# ExtBoard-001_2024-04-03.net
KiCad netlist of a schematic drawn in EasyEDA Pro
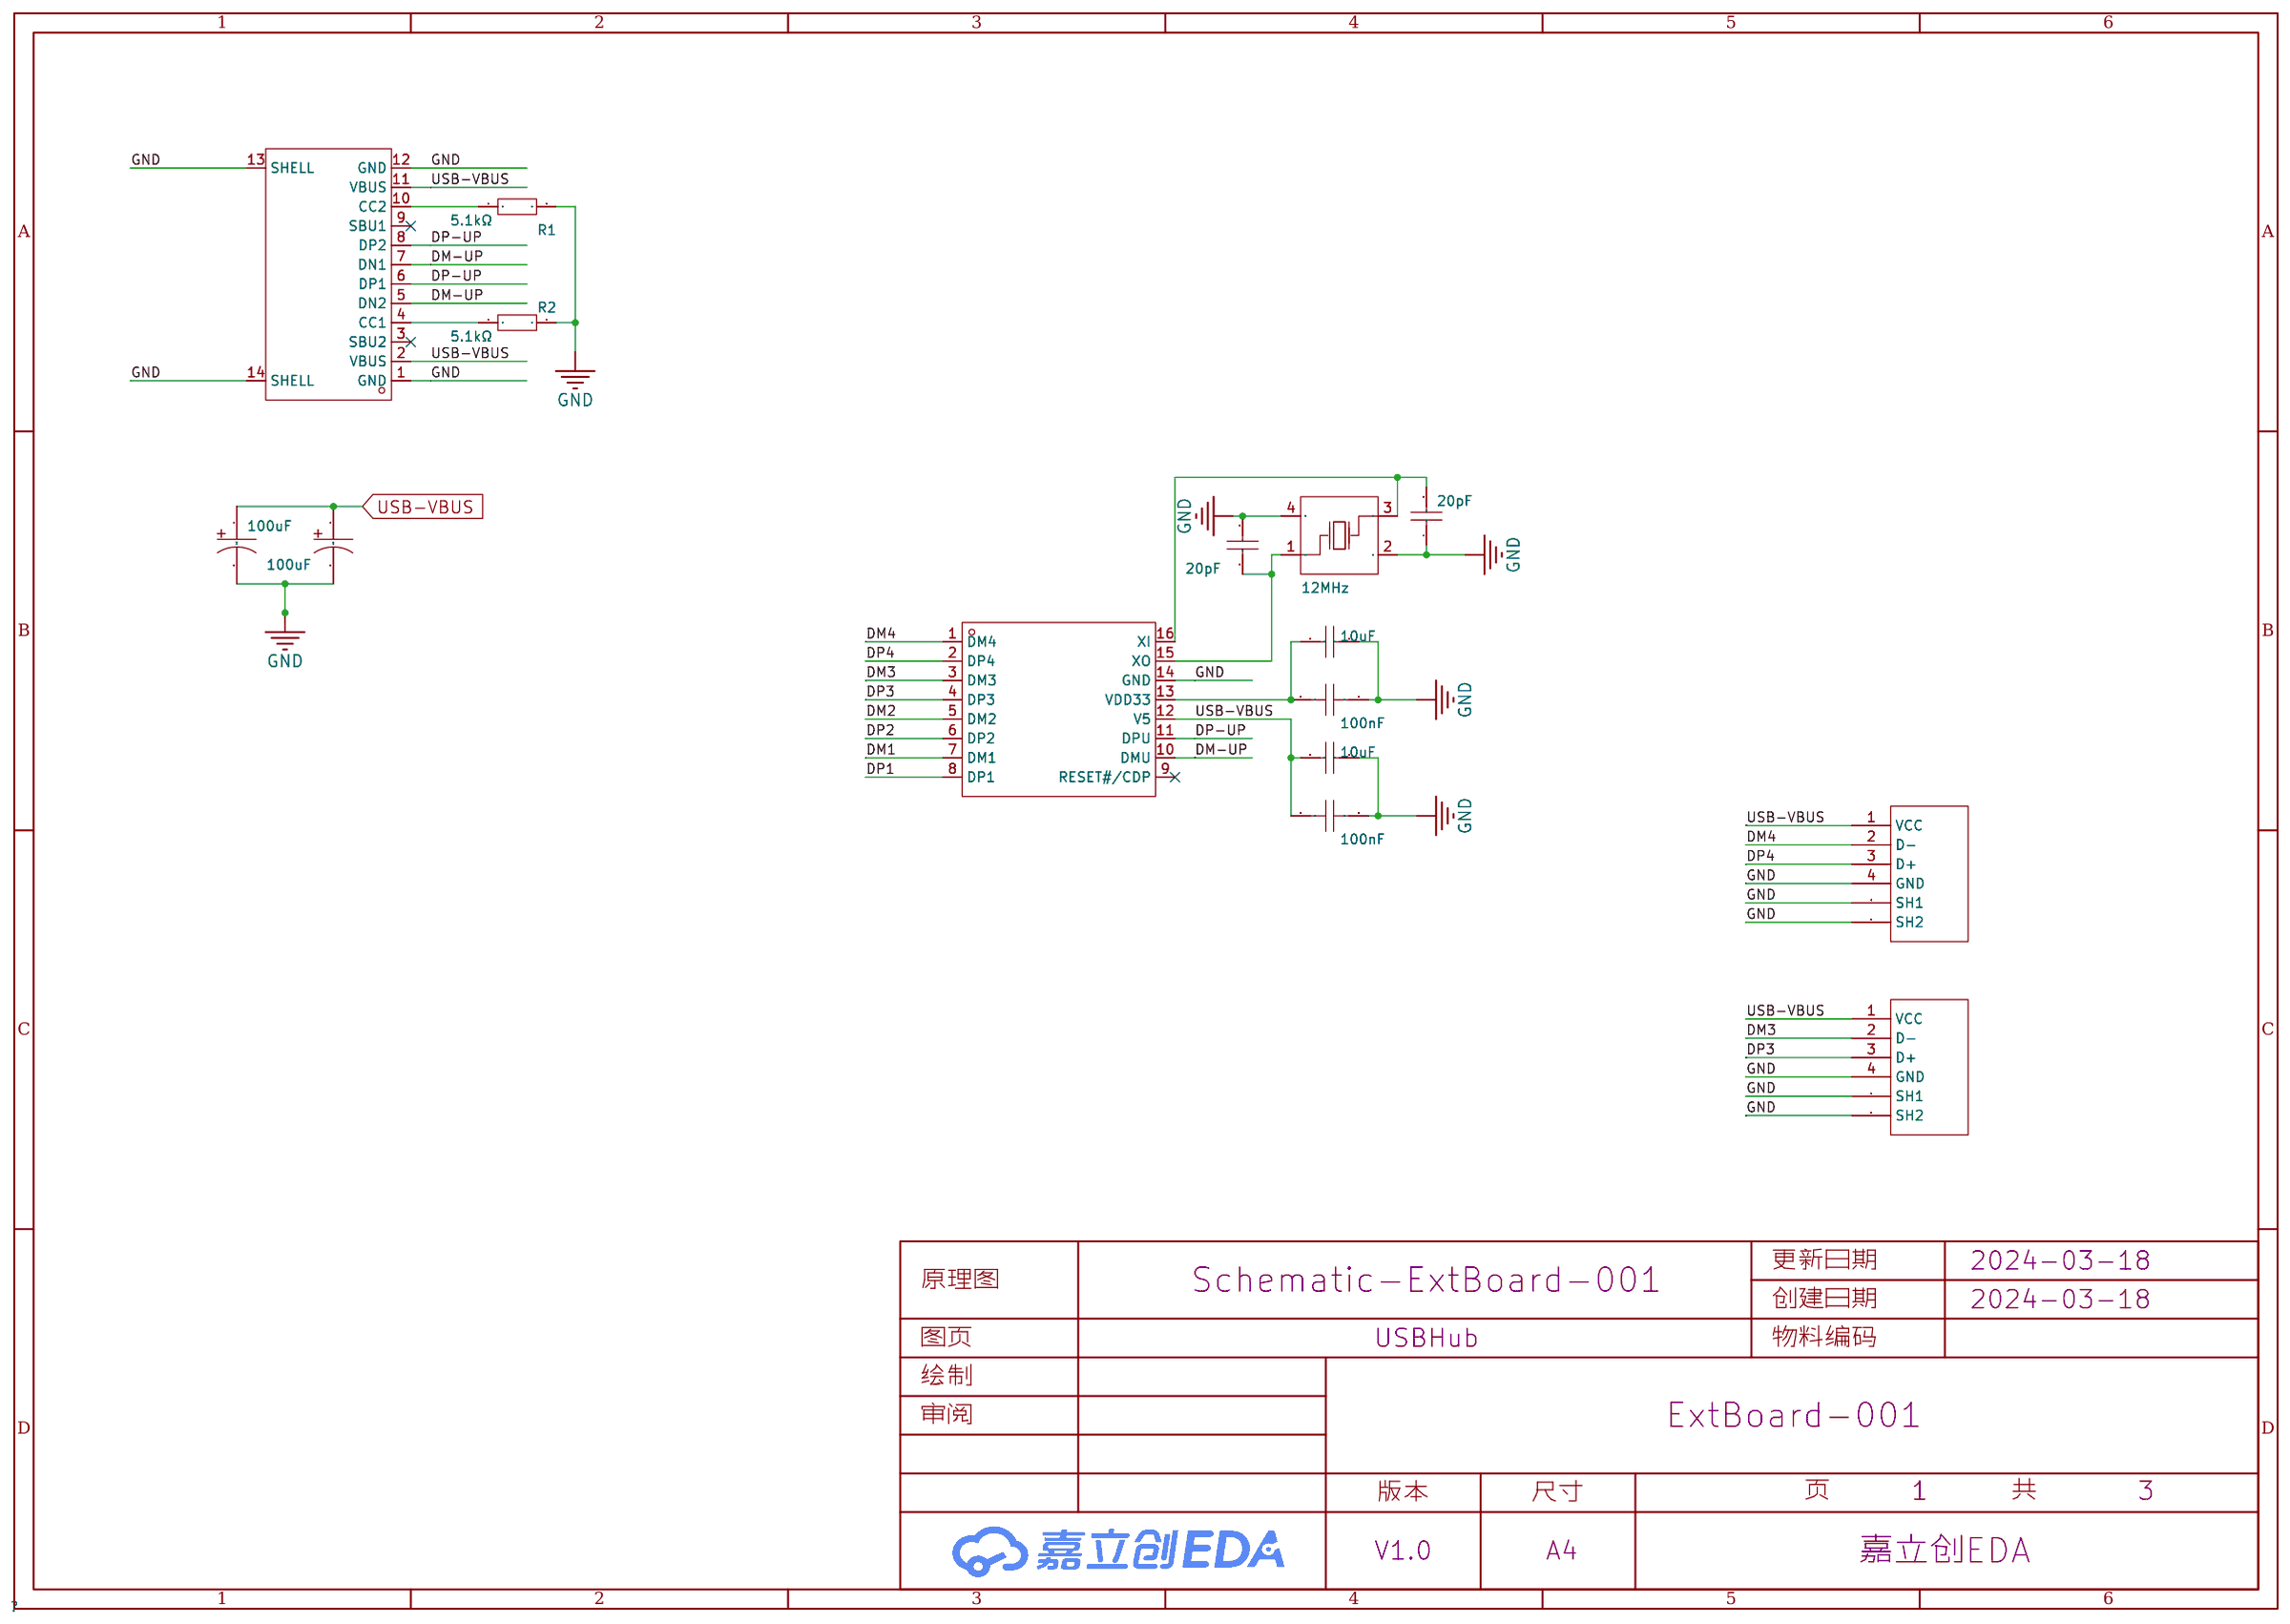
[diagram p0: USBHub]
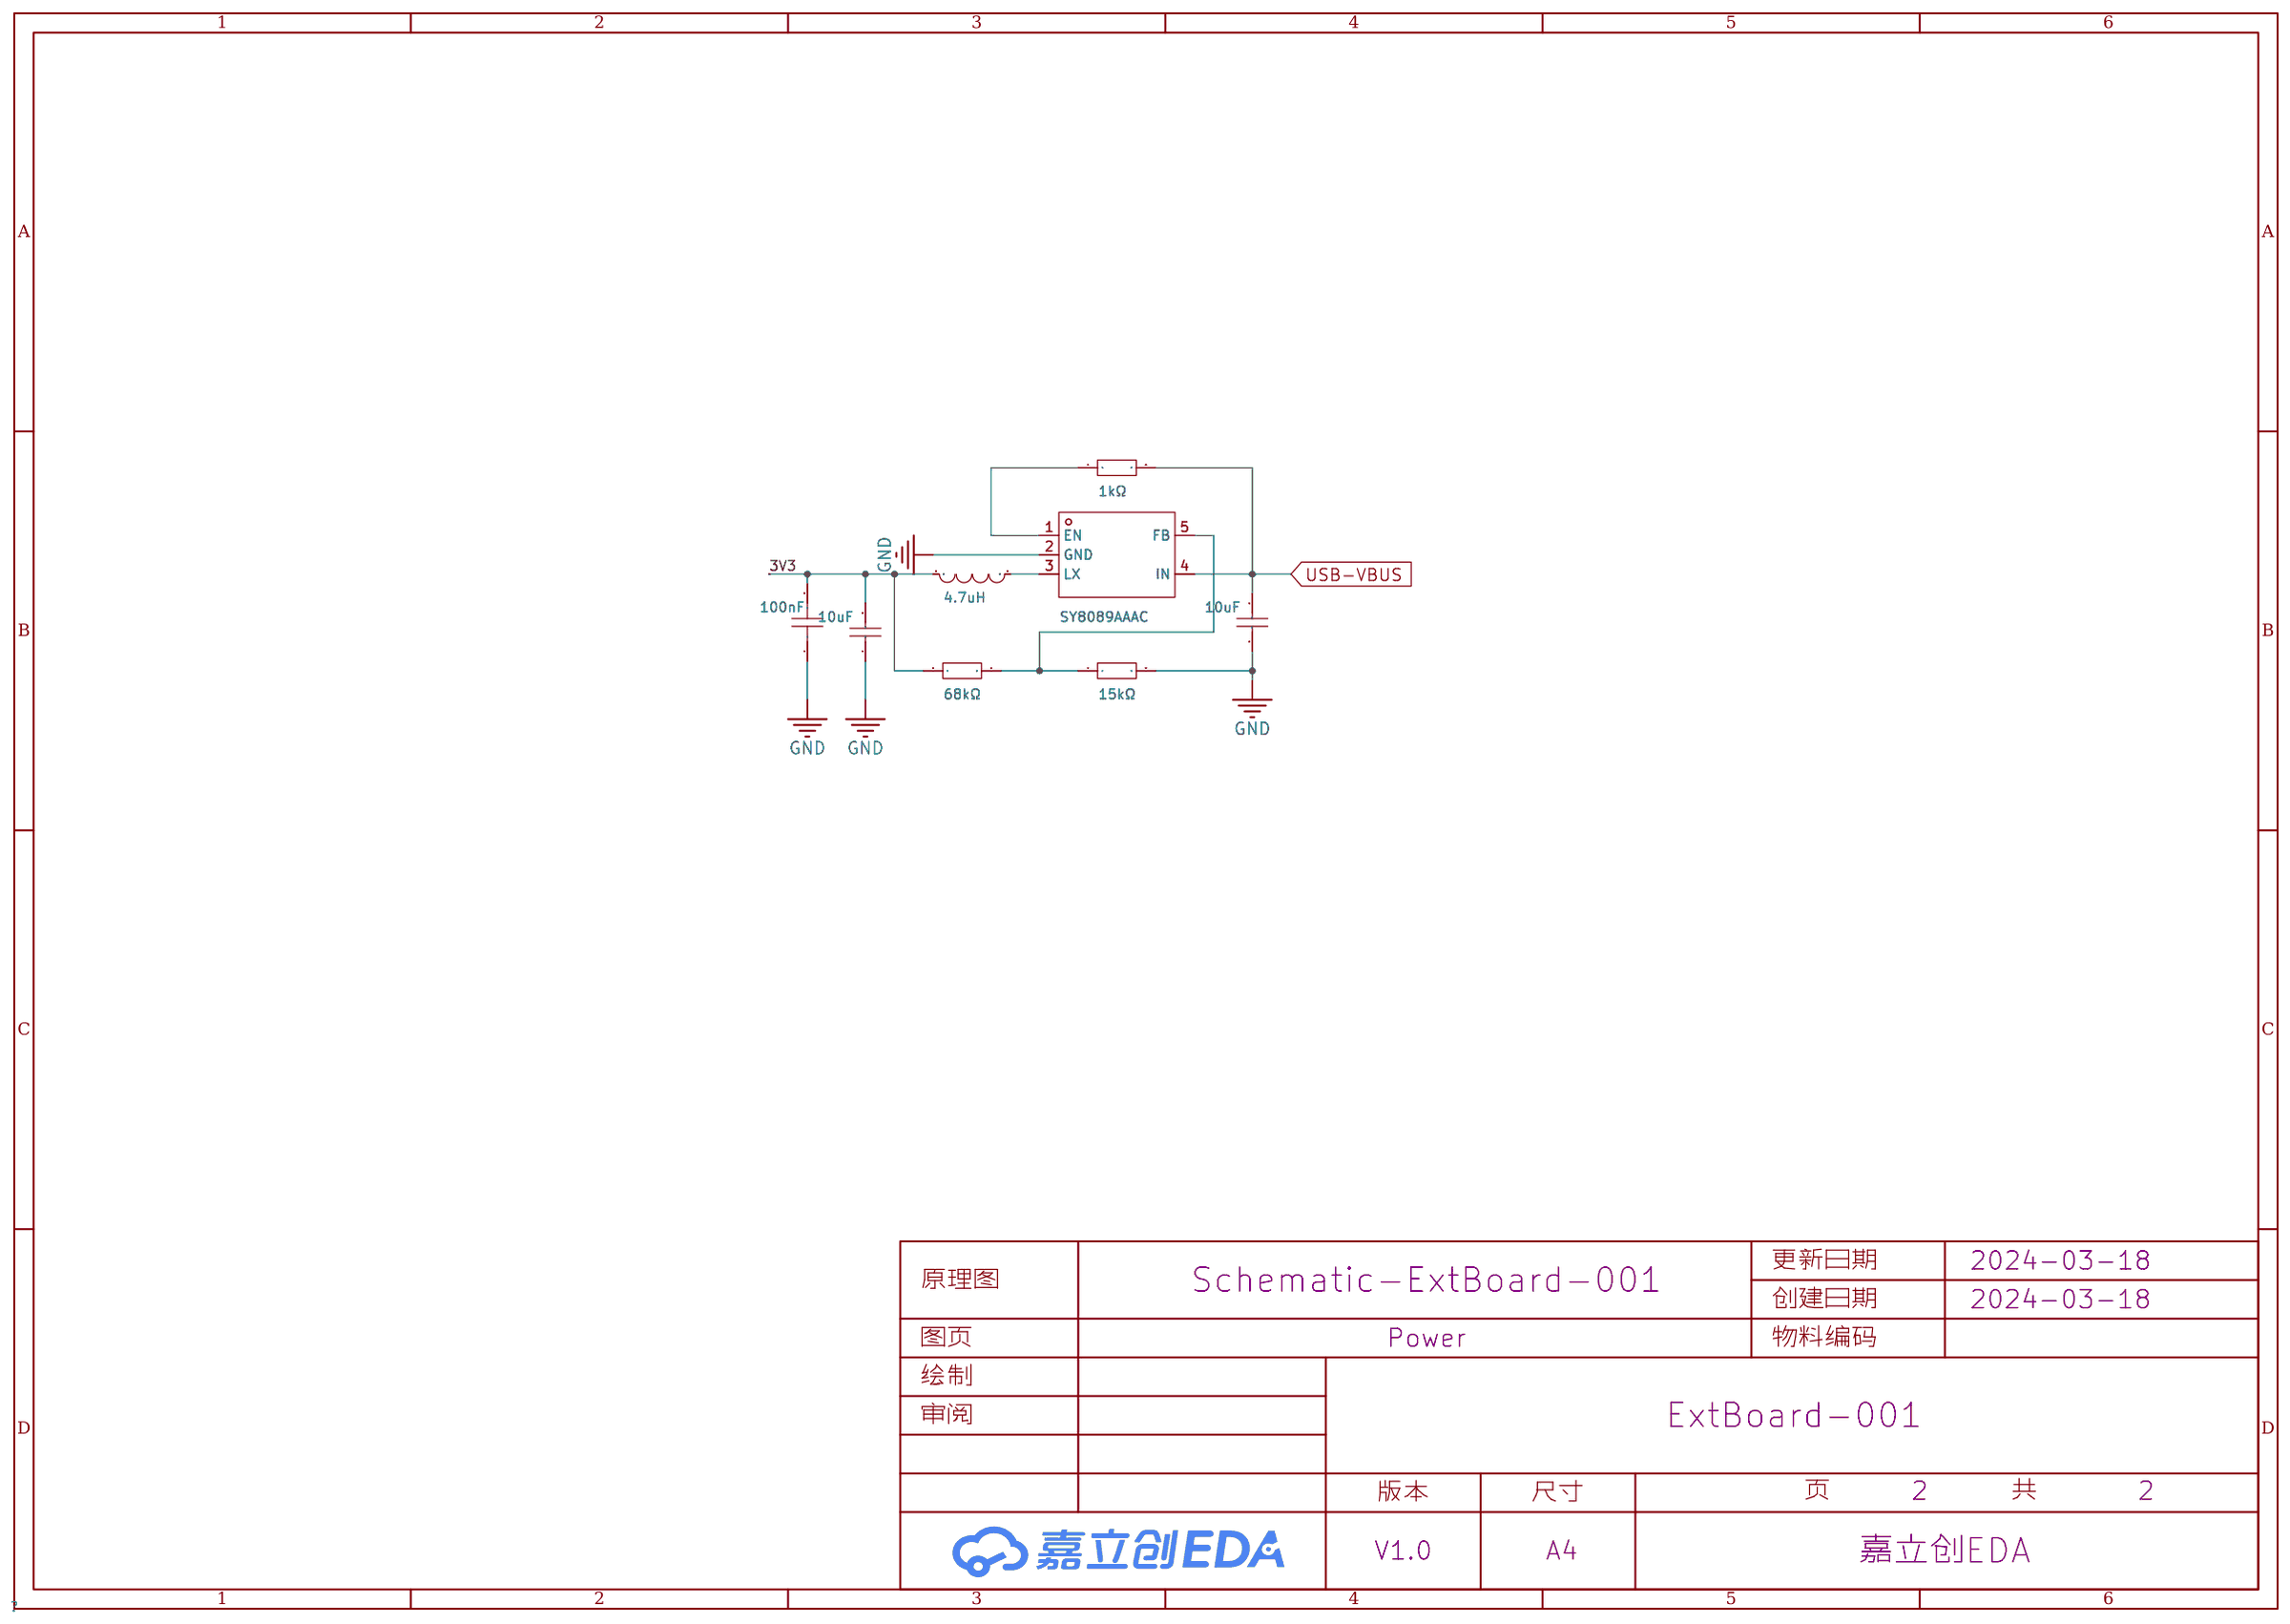
[diagram p1: Power]
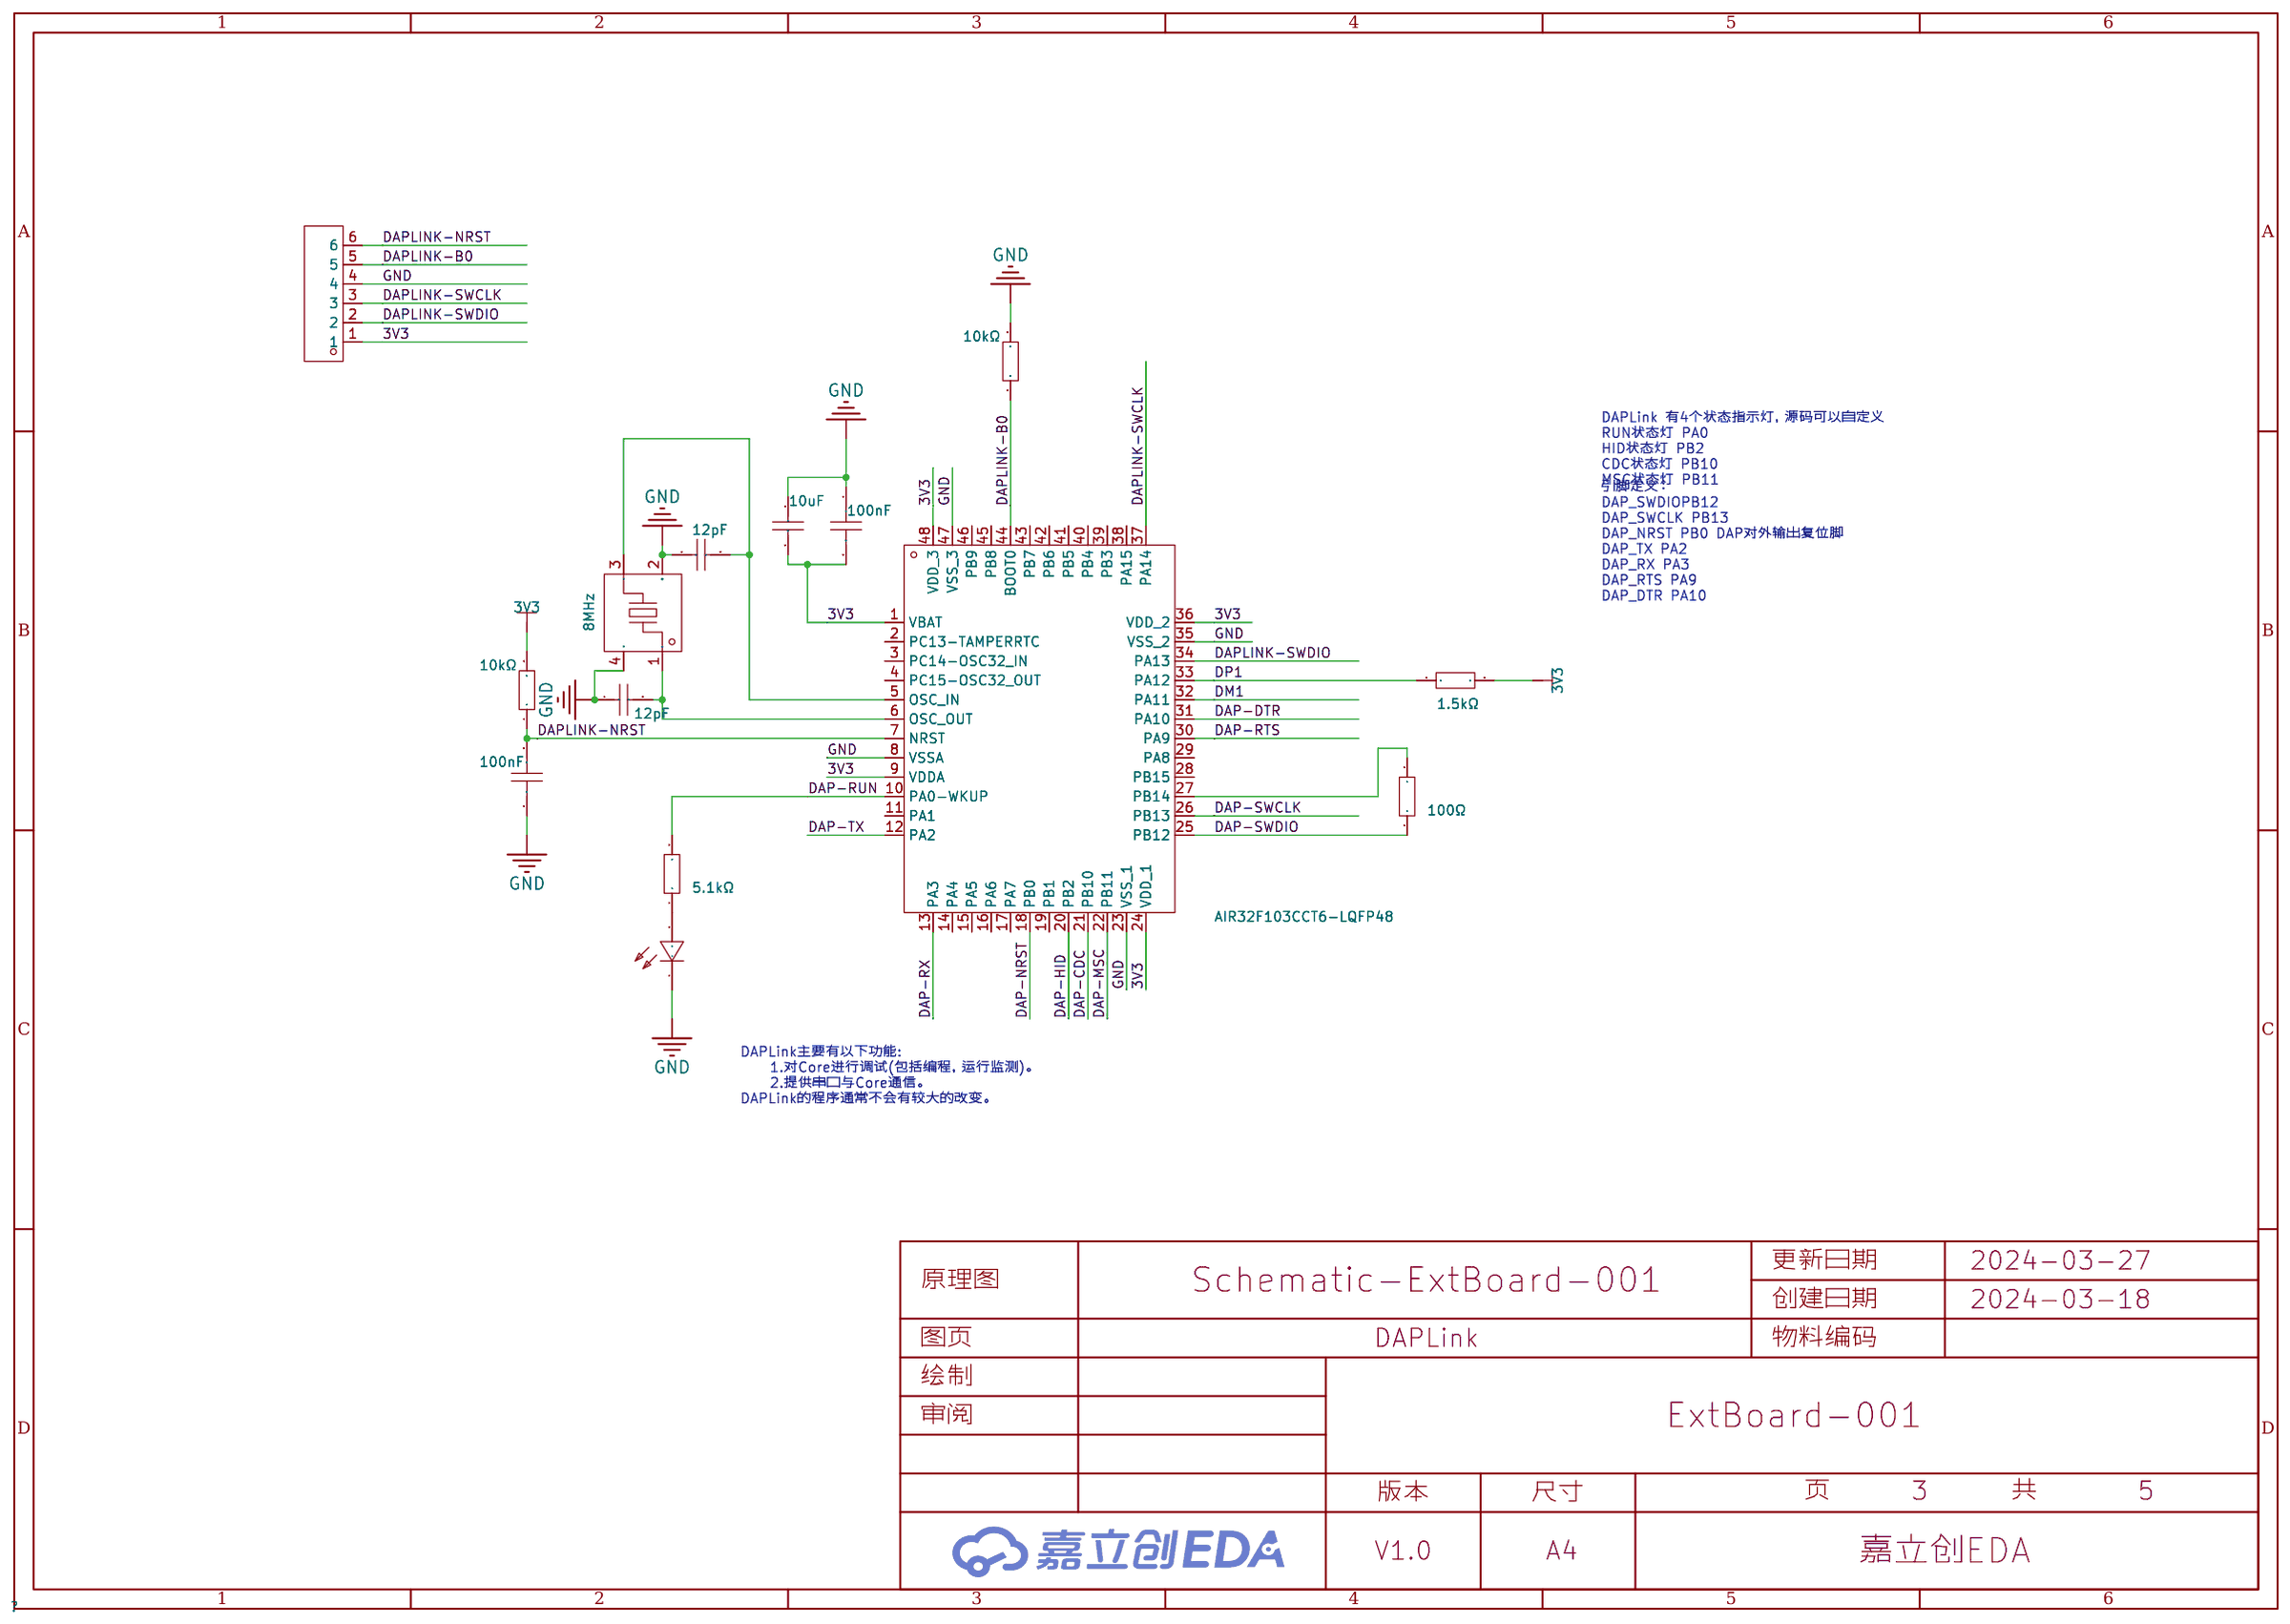
[diagram p2: DAPLink]
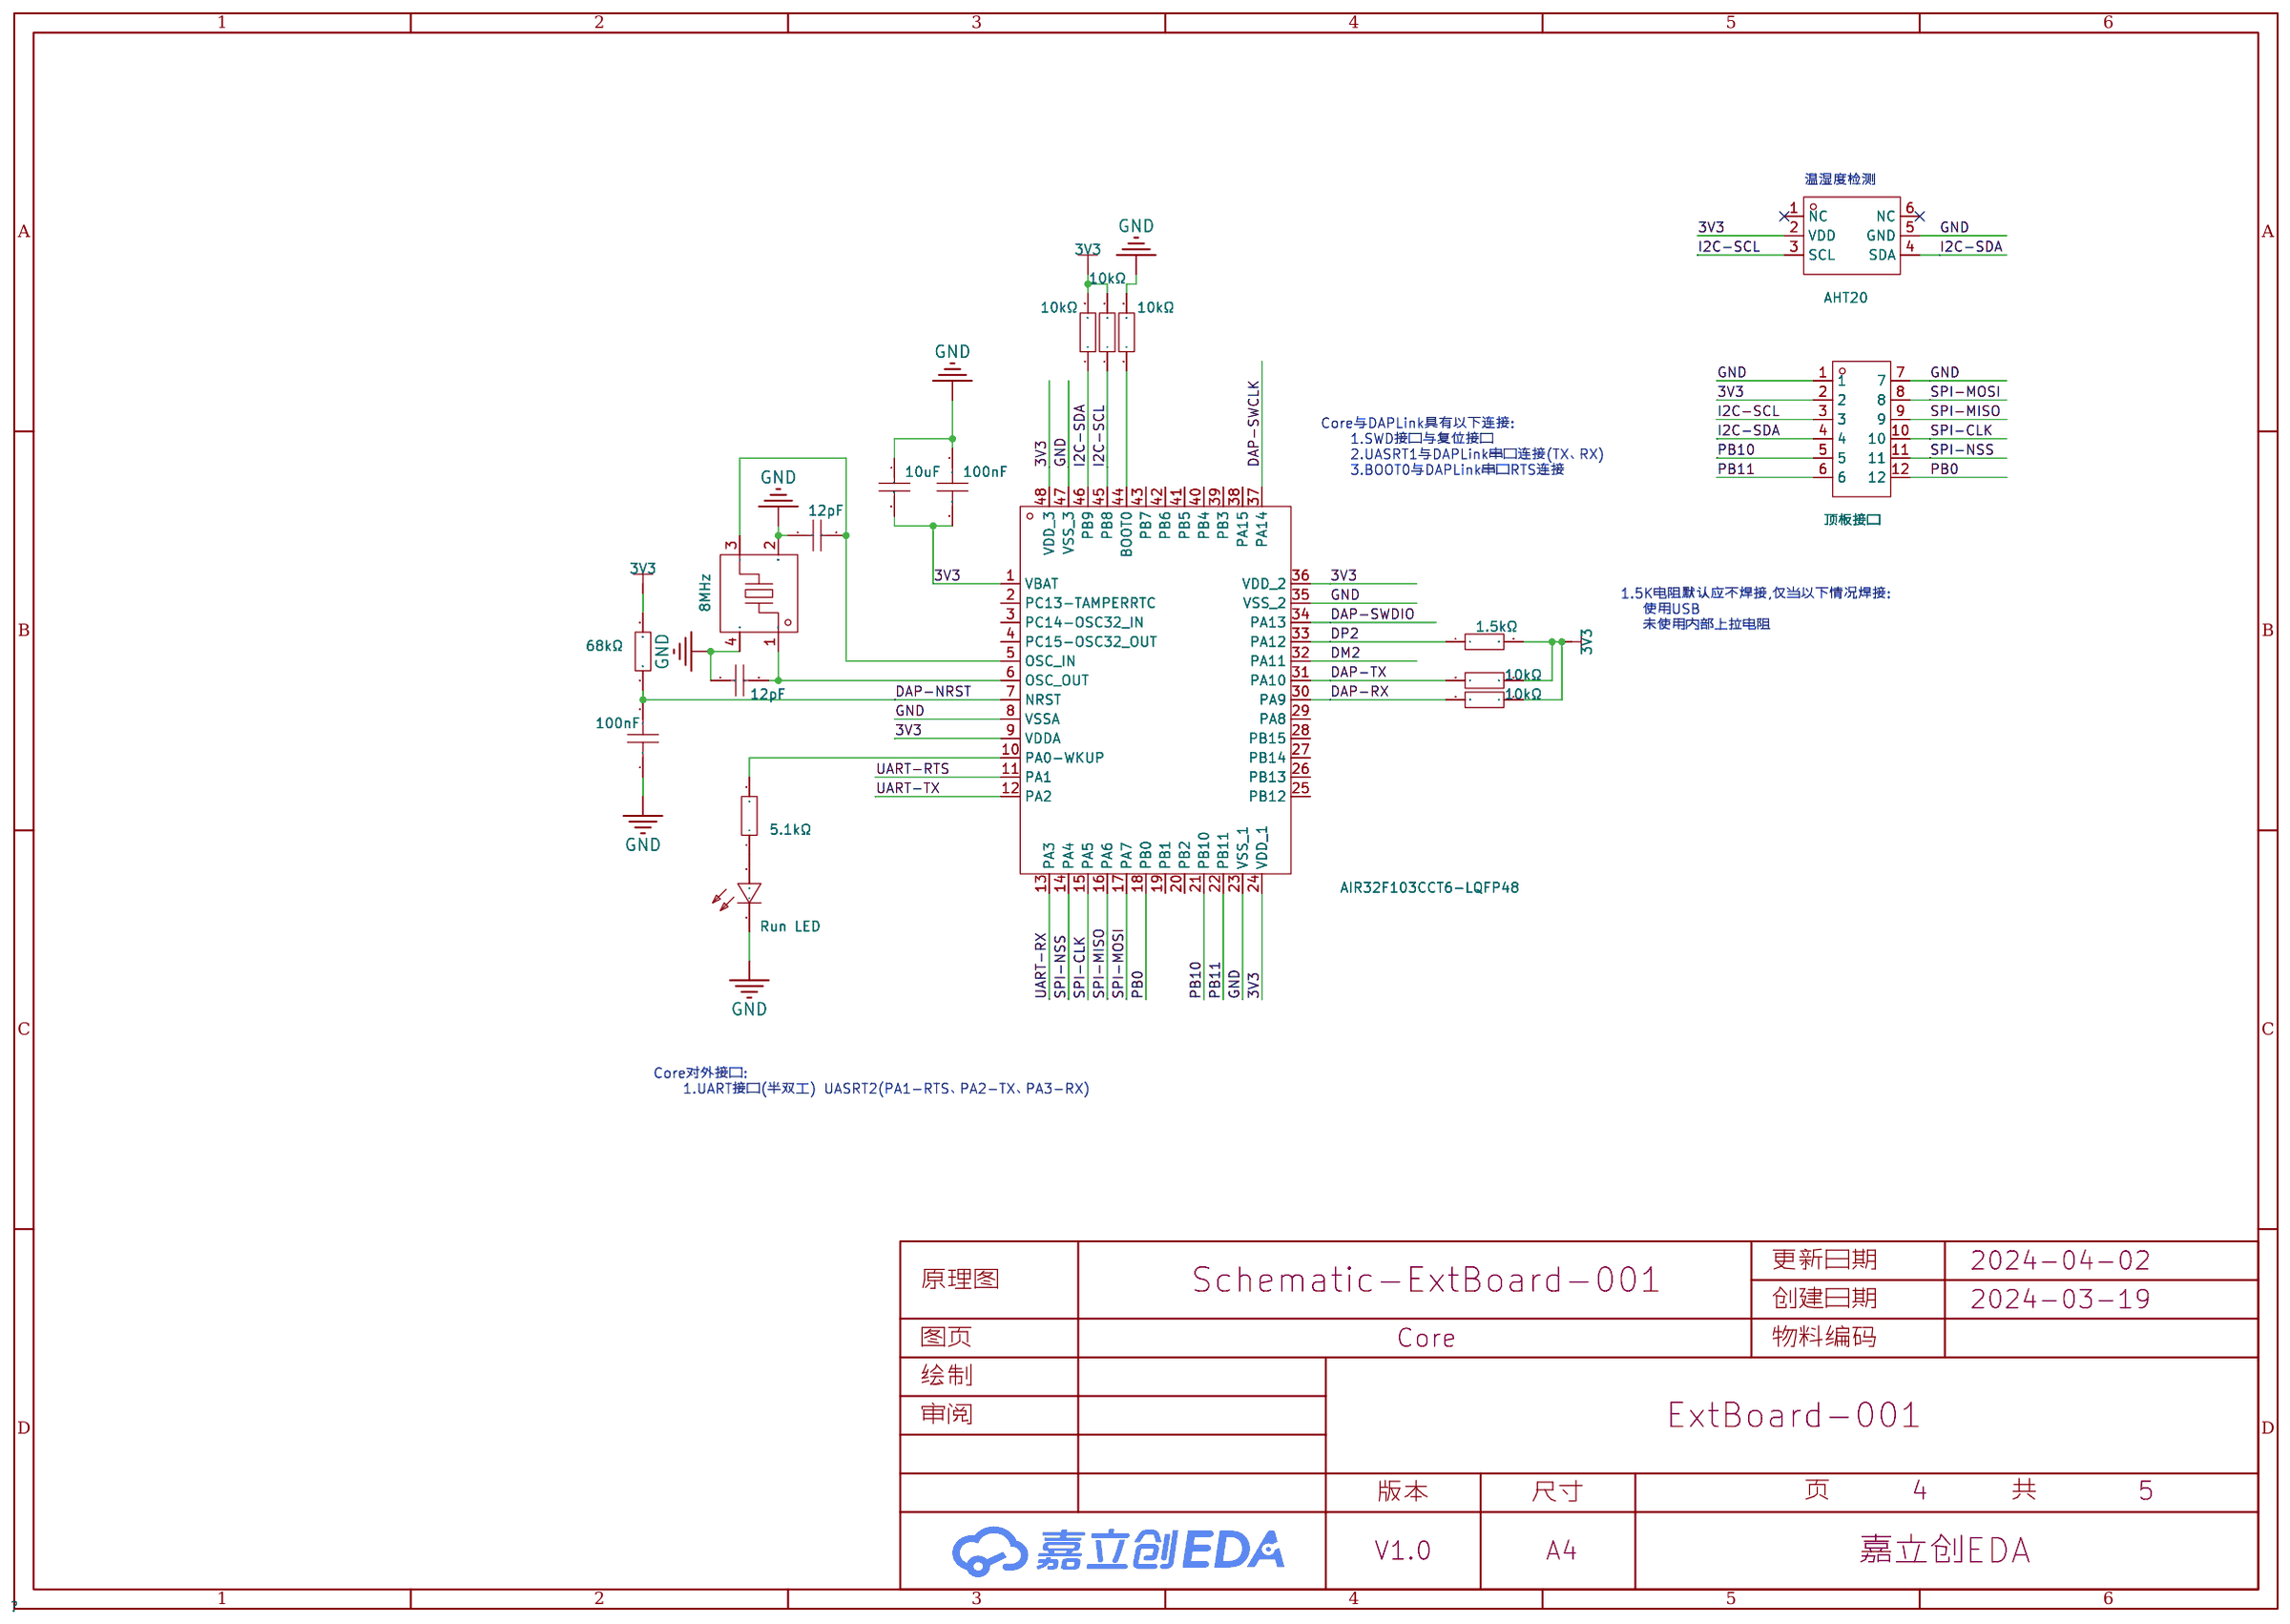
[diagram p3: Core]
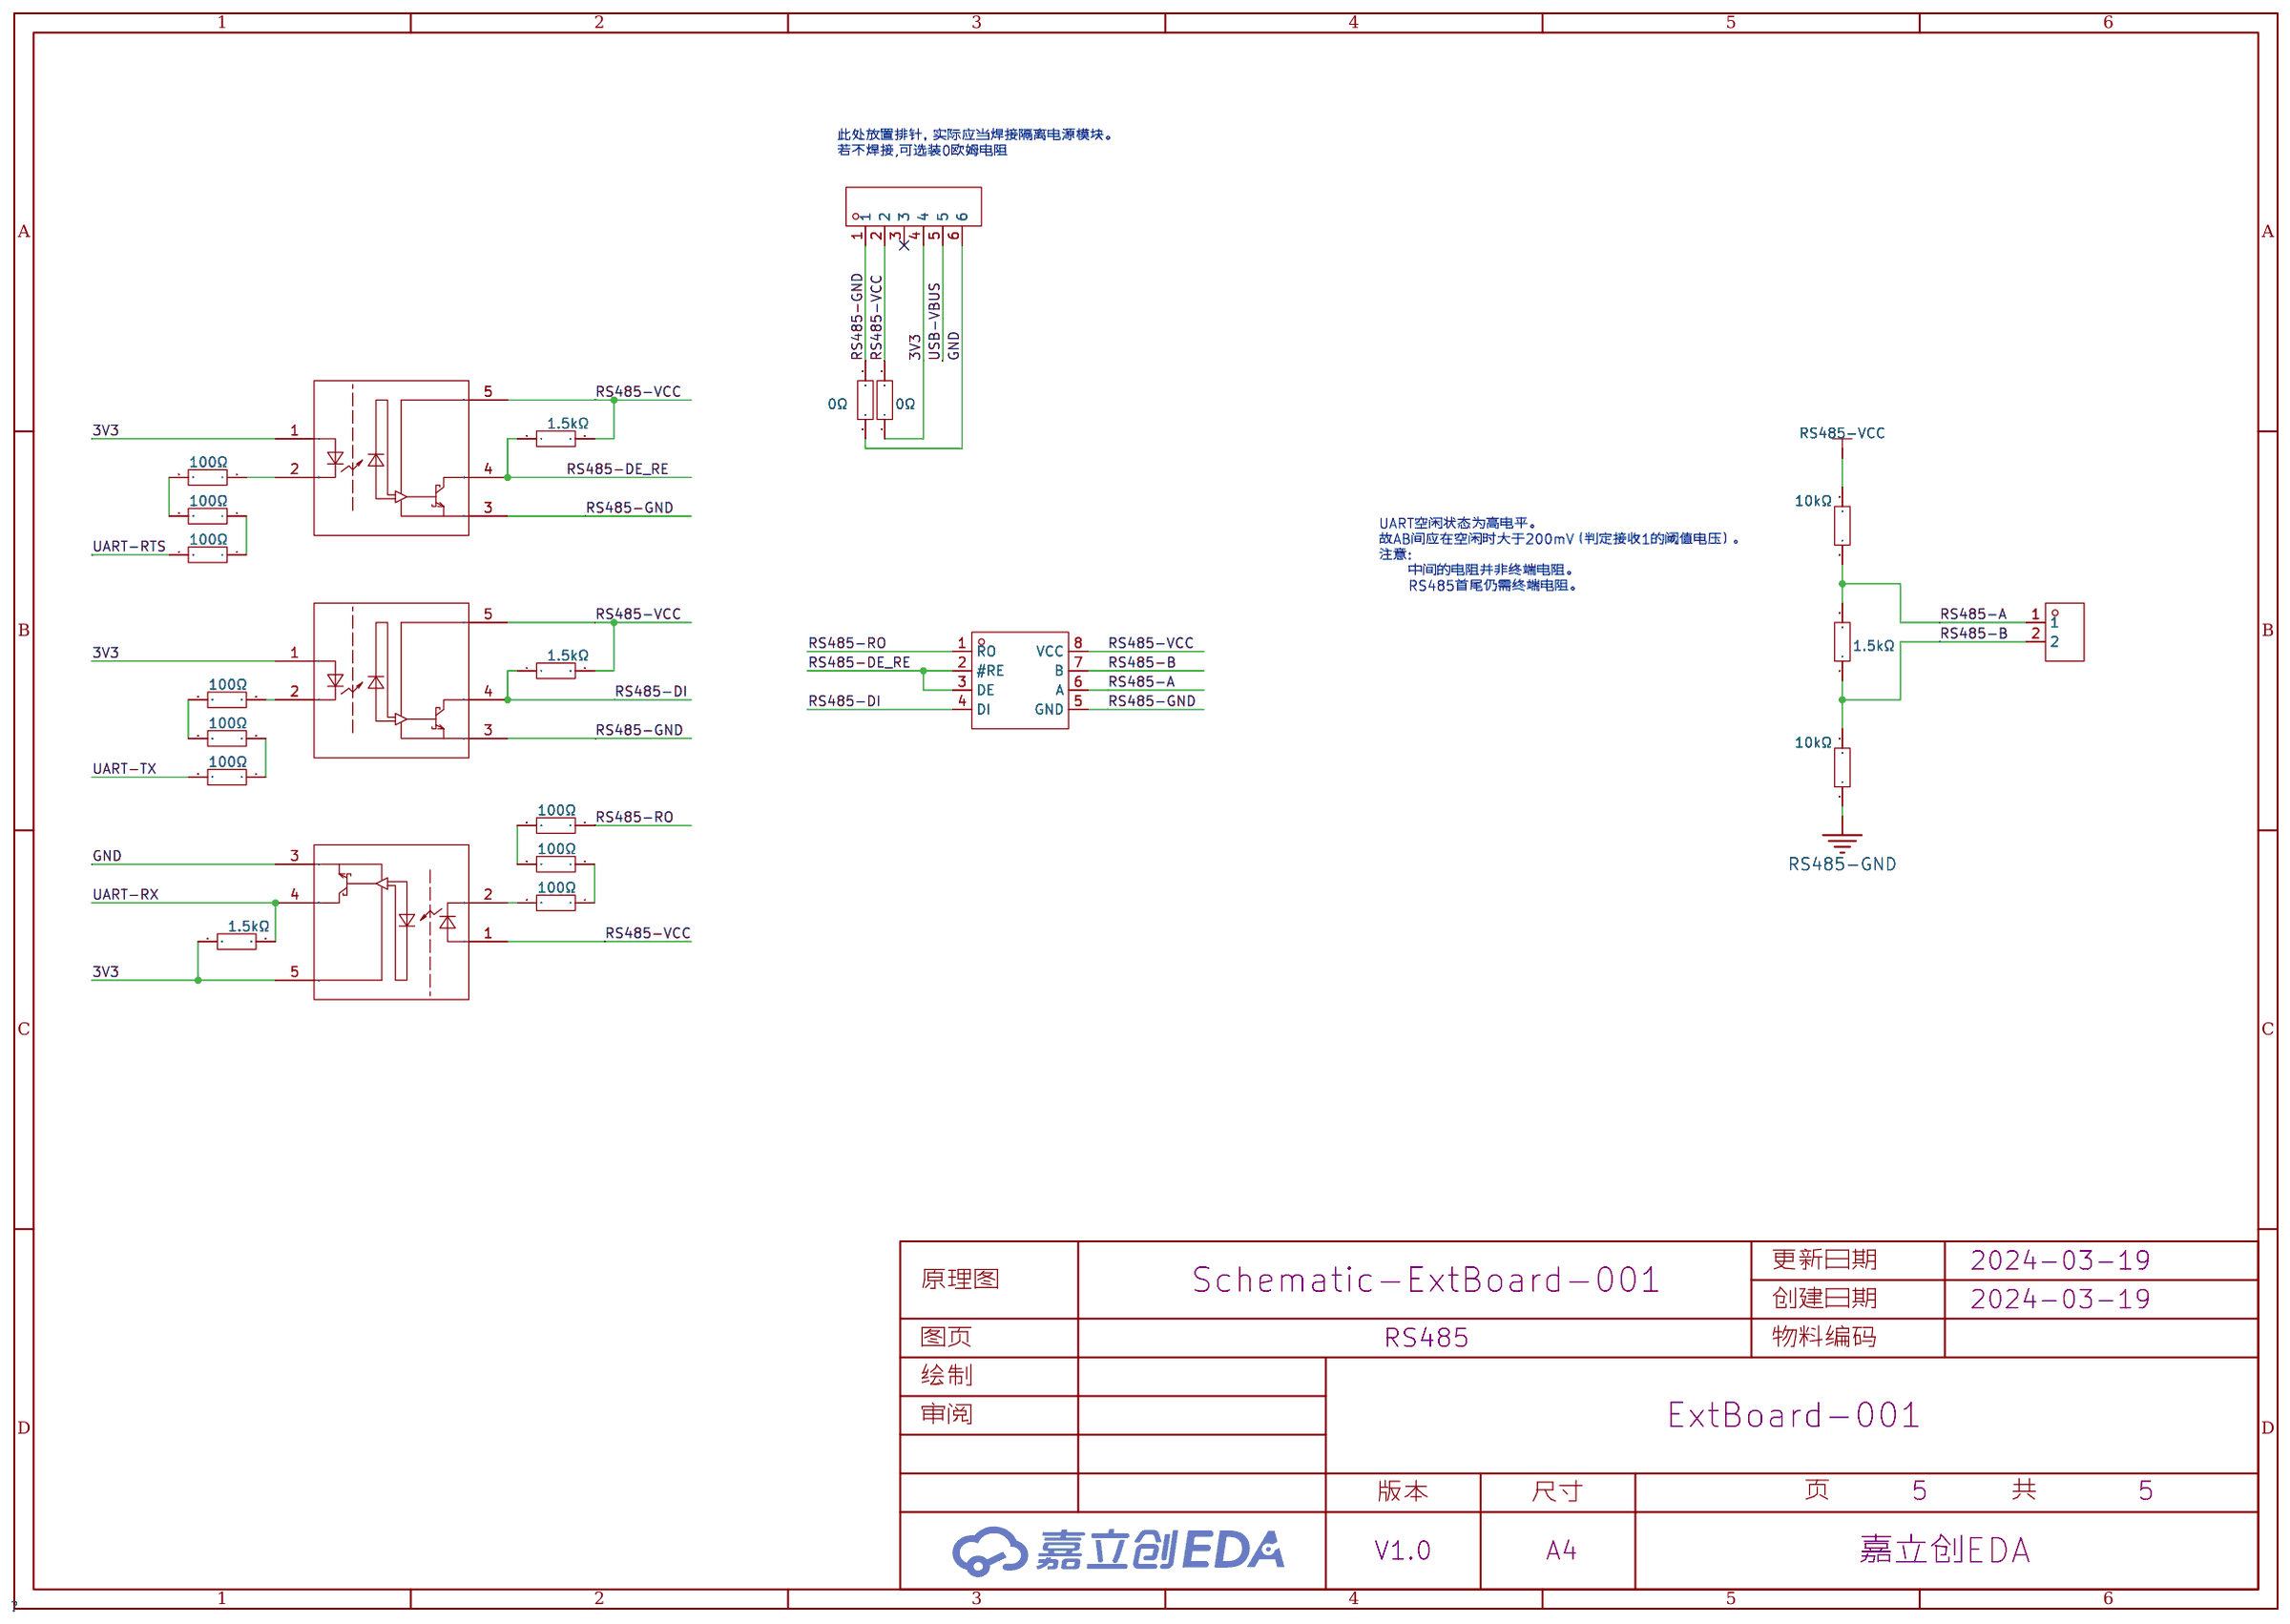
[diagram p4: RS485]

(export (version "E")
  (design (tool "Eeschema 10.0.6"))
  (components
    (comp (ref "C3")
      (value "100nF")
      (footprint "easyedapro:C0402")
      (description "容值:100nF;精度:±10%;额定电压:16V;材质(温度系数):X7R;")
      (fields
        (field (name "Manufacturer Part") "CC0402KRX7R7BB104")
        (field (name "Manufacturer") "YAGEO(国巨)")
      )
      (libsource (lib "easyedapro") (part "CC0402KRX7R7BB104"))
    )
    (comp (ref "C4")
      (value "10uF")
      (footprint "easyedapro:C0402")
      (description "容值:10uF;精度:±20%;额定电压:6.3V;材质(温度系数):X5R;")
      (fields
        (field (name "Manufacturer Part") "CL05A106MQ5NUNC")
        (field (name "Manufacturer") "SAMSUNG(三星)")
      )
      (libsource (lib "easyedapro") (part "CL05A106MQ5NUNC"))
    )
    (comp (ref "C5")
      (value "10uF")
      (footprint "easyedapro:C0402")
      (description "容值:10uF;精度:±20%;额定电压:6.3V;材质(温度系数):X5R;")
      (fields
        (field (name "Manufacturer Part") "CL05A106MQ5NUNC")
        (field (name "Manufacturer") "SAMSUNG(三星)")
      )
      (libsource (lib "easyedapro") (part "CL05A106MQ5NUNC"))
    )
    (comp (ref "C6")
      (value "100nF")
      (footprint "easyedapro:C0402")
      (description "容值:100nF;精度:±10%;额定电压:16V;材质(温度系数):X7R;")
      (fields
        (field (name "Manufacturer Part") "CC0402KRX7R7BB104")
        (field (name "Manufacturer") "YAGEO(国巨)")
      )
      (libsource (lib "easyedapro") (part "CC0402KRX7R7BB104"))
    )
    (comp (ref "C7")
      (value "20pF")
      (footprint "easyedapro:C0402")
      (description "容值:20pF;精度:±5%;额定电压:50V;材质(温度系数):C0G;")
      (fields (field (name "Manufacturer Part") "0402CG200J500NT") (field (name "Manufacturer") "FH(风华)"))
      (libsource (lib "easyedapro") (part "0402CG200J500NT"))
    )
    (comp (ref "C8")
      (value "20pF")
      (footprint "easyedapro:C0402")
      (description "容值:20pF;精度:±5%;额定电压:50V;材质(温度系数):C0G;")
      (fields (field (name "Manufacturer Part") "0402CG200J500NT") (field (name "Manufacturer") "FH(风华)"))
      (libsource (lib "easyedapro") (part "0402CG200J500NT"))
    )
    (comp (ref "C22")
      (value "100uF")
      (footprint "easyedapro:CAP-SMD_BD6.3-L6.6-W6.6-FD")
      (description "容值:100uF;精度:±20%;额定电压:16V;纹波电流:-;等效串联电阻:-;")
      (fields (field (name "Manufacturer Part") "VEZ101M1CTR-0605") (field (name "Manufacturer") "lelon(立隆)"))
      (libsource (lib "easyedapro") (part "VEZ101M1C0605-TRO"))
    )
    (comp (ref "C23")
      (value "100uF")
      (footprint "easyedapro:CAP-SMD_BD6.3-L6.6-W6.6-FD")
      (description "容值:100uF;精度:±20%;额定电压:16V;纹波电流:-;等效串联电阻:-;")
      (fields (field (name "Manufacturer Part") "VEZ101M1CTR-0605") (field (name "Manufacturer") "lelon(立隆)"))
      (libsource (lib "easyedapro") (part "VEZ101M1C0605-TRO"))
    )
    (comp (ref "R1")
      (value "5.1kΩ")
      (footprint "easyedapro:R0402")
      (description "阻值:5.1kΩ;精度:±1%;功率:62.5mW;温度系数:±100ppm/°C;电阻类型:厚膜电阻;")
      (fields
        (field (name "Manufacturer Part") "0402WGF5101TCE")
        (field (name "Manufacturer") "UNI-ROYAL(厚声)")
      )
      (libsource (lib "easyedapro") (part "0402WGF5101TCE"))
    )
    (comp (ref "R2")
      (value "5.1kΩ")
      (footprint "easyedapro:R0402")
      (description "阻值:5.1kΩ;精度:±1%;功率:62.5mW;温度系数:±100ppm/°C;电阻类型:厚膜电阻;")
      (fields
        (field (name "Manufacturer Part") "0402WGF5101TCE")
        (field (name "Manufacturer") "UNI-ROYAL(厚声)")
      )
      (libsource (lib "easyedapro") (part "0402WGF5101TCE"))
    )
    (comp (ref "U1")
      (value "CH334R")
      (footprint "easyedapro:QSOP-16_L4.9-W3.9-P0.64-LS6.0-BL")
      (fields (field (name "Manufacturer") "WCH(南京沁恒)"))
      (libsource (lib "easyedapro") (part "CH334R"))
    )
    (comp (ref "USB1")
      (value "TYPE-C 16PIN 2MD(073)")
      (footprint "easyedapro:USB-C-SMD_TYPE-C-6PIN-2MD-073")
      (description "连接器类型:Type-C;标准:-;公母:母;端口数量:1;触点数量:16P;安装方式:卧贴;额定电流 - 电源:5A;工作温度范围:-25°C~+85°C;")
      (fields (field (name "Manufacturer") "SHOU HAN(首韩)"))
      (libsource (lib "easyedapro") (part "TYPE-C 16PIN 2MD(073)"))
    )
    (comp (ref "USB2")
      (value "U-USBAR04P-F002")
      (footprint "easyedapro:USB-A-TH_USB-302-T")
      (description "连接器类型:Type-A;标准:USB 2.0;公母:母;端口数量:1;触点数量:4P;安装方式:弯插;额定电流 - 电源:1.5A;工作温度范围:0°C~+50°C;")
      (fields (field (name "Manufacturer") "Ckmtw(灿科盟)"))
      (libsource (lib "easyedapro") (part "U-USBAR04P-F001"))
    )
    (comp (ref "USB3")
      (value "U-USBAR04P-F002")
      (footprint "easyedapro:USB-A-TH_USB-302-T")
      (description "连接器类型:Type-A;标准:USB 2.0;公母:母;端口数量:1;触点数量:4P;安装方式:弯插;额定电流 - 电源:1.5A;工作温度范围:0°C~+50°C;")
      (fields (field (name "Manufacturer") "Ckmtw(灿科盟)"))
      (libsource (lib "easyedapro") (part "U-USBAR04P-F001"))
    )
    (comp (ref "X1")
      (value "12MHz")
      (footprint "easyedapro:OSC-SMD_4P-L3.2-W2.5-BL")
      (description "晶振类型:贴片晶振;频率:12MHz;常温频差:±10ppm;外接负载电容:20pF;频率稳定度(全温):±30ppm;")
      (fields (field (name "Manufacturer Part") "X322512MSB4SI") (field (name "Manufacturer") "YXC(扬兴晶振)"))
      (libsource (lib "easyedapro") (part "X322512MSB4SI"))
    )
    (comp (ref "C15")
      (value "10uF")
      (footprint "easyedapro:C0402")
      (description "容值:10uF;精度:±20%;额定电压:6.3V;材质(温度系数):X5R;")
      (fields
        (field (name "Manufacturer Part") "CL05A106MQ5NUNC")
        (field (name "Manufacturer") "SAMSUNG(三星)")
      )
      (libsource (lib "easyedapro") (part "CL05A106MQ5NUNC"))
    )
    (comp (ref "C16")
      (value "10uF")
      (footprint "easyedapro:C0402")
      (description "容值:10uF;精度:±20%;额定电压:6.3V;材质(温度系数):X5R;")
      (fields
        (field (name "Manufacturer Part") "CL05A106MQ5NUNC")
        (field (name "Manufacturer") "SAMSUNG(三星)")
      )
      (libsource (lib "easyedapro") (part "CL05A106MQ5NUNC"))
    )
    (comp (ref "C17")
      (value "100nF")
      (footprint "easyedapro:C0402")
      (description "容值:100nF;精度:±10%;额定电压:16V;材质(温度系数):X7R;")
      (fields
        (field (name "Manufacturer Part") "CC0402KRX7R7BB104")
        (field (name "Manufacturer") "YAGEO(国巨)")
      )
      (libsource (lib "easyedapro") (part "CC0402KRX7R7BB104"))
    )
    (comp (ref "L1")
      (value "4.7uH")
      (footprint "easyedapro:IND-SMD_L4.0-W4.0")
      (description "直流电阻(DCR):78mΩ;精度:±20%;电感值:4.7uH;额定电流:2A;")
      (fields (field (name "Manufacturer Part") "SWPA4030S4R7MT") (field (name "Manufacturer") "Sunlord(顺络)"))
      (libsource (lib "easyedapro") (part "SWPA4030S4R7MT"))
    )
    (comp (ref "R11")
      (value "1kΩ")
      (footprint "easyedapro:R0402")
      (description "阻值:1kΩ;精度:±1%;功率:62.5mW;温度系数:±100ppm/°C;电阻类型:厚膜电阻;")
      (fields
        (field (name "Manufacturer Part") "0402WGF1001TCE")
        (field (name "Manufacturer") "UNI-ROYAL(厚声)")
      )
      (libsource (lib "easyedapro") (part "0402WGF1001TCE"))
    )
    (comp (ref "R12")
      (value "68kΩ")
      (footprint "easyedapro:R0402")
      (description "阻值:68kΩ;精度:±1%;功率:62.5mW;温度系数:±100ppm/°C;电阻类型:厚膜电阻;")
      (fields
        (field (name "Manufacturer Part") "0402WGF6802TCE")
        (field (name "Manufacturer") "UNI-ROYAL(厚声)")
      )
      (libsource (lib "easyedapro") (part "0402WGF6802TCE"))
    )
    (comp (ref "R13")
      (value "15kΩ")
      (footprint "easyedapro:R0402")
      (description "阻值:15kΩ;精度:±1%;功率:62.5mW;温度系数:±100ppm/°C;电阻类型:厚膜电阻;")
      (fields
        (field (name "Manufacturer Part") "0402WGF1502TCE")
        (field (name "Manufacturer") "UNI-ROYAL(厚声)")
      )
      (libsource (lib "easyedapro") (part "0402WGF1502TCE"))
    )
    (comp (ref "U3")
      (value "SY8089AAAC")
      (footprint "easyedapro:SOT-23-5_L3.0-W1.7-P0.95-LS2.8-BR")
      (description "功能类型:降压型;同步整流:-;输出通道数:-;拓扑结构:-;输入电压:-;输出电流(最大值):-;开关频率:-;")
      (fields (field (name "Manufacturer") "silergy(矽力杰)"))
      (libsource (lib "easyedapro") (part "SY8089AAAC"))
    )
    (comp (ref "C24")
      (value "100nF")
      (footprint "easyedapro:C0402")
      (description "容值:100nF;精度:±10%;额定电压:16V;材质(温度系数):X7R;")
      (fields
        (field (name "Manufacturer Part") "CC0402KRX7R7BB104")
        (field (name "Manufacturer") "YAGEO(国巨)")
      )
      (libsource (lib "easyedapro") (part "CC0402KRX7R7BB104"))
    )
    (comp (ref "C25")
      (value "12pF")
      (footprint "easyedapro:C0402")
      (description "容值:12pF;精度:±5%;额定电压:50V;材质(温度系数):C0G;")
      (fields (field (name "Manufacturer Part") "0402CG120J500NT") (field (name "Manufacturer") "FH(风华)"))
      (libsource (lib "easyedapro") (part "0402CG120J500NT"))
    )
    (comp (ref "C26")
      (value "12pF")
      (footprint "easyedapro:C0402")
      (description "容值:12pF;精度:±5%;额定电压:50V;材质(温度系数):C0G;")
      (fields (field (name "Manufacturer Part") "0402CG120J500NT") (field (name "Manufacturer") "FH(风华)"))
      (libsource (lib "easyedapro") (part "0402CG120J500NT"))
    )
    (comp (ref "C30")
      (value "10uF")
      (footprint "easyedapro:C0402")
      (description "容值:10uF;精度:±20%;额定电压:6.3V;材质(温度系数):X5R;")
      (fields
        (field (name "Manufacturer Part") "CL05A106MQ5NUNC")
        (field (name "Manufacturer") "SAMSUNG(三星)")
      )
      (libsource (lib "easyedapro") (part "CL05A106MQ5NUNC"))
    )
    (comp (ref "C31")
      (value "100nF")
      (footprint "easyedapro:C0402")
      (description "容值:100nF;精度:±10%;额定电压:16V;材质(温度系数):X7R;")
      (fields
        (field (name "Manufacturer Part") "CC0402KRX7R7BB104")
        (field (name "Manufacturer") "YAGEO(国巨)")
      )
      (libsource (lib "easyedapro") (part "CC0402KRX7R7BB104"))
    )
    (comp (ref "H1")
      (value "PZ254-1-06-Z-8.5")
      (footprint "easyedapro:HDR-TH_06P-P2.54-V-M")
      (fields (field (name "Manufacturer") "HCTL(华灿天禄)"))
      (libsource (lib "easyedapro") (part "PZ254-1-06-Z-8.5"))
    )
    (comp (ref "LED1")
      (value "NCD0603R1")
      (footprint "easyedapro:LED0603-RD_RED")
      (fields (field (name "Manufacturer") "国星光电"))
      (libsource (lib "easyedapro") (part "FC-DA1608HRK-620D"))
    )
    (comp (ref "R4")
      (value "10kΩ")
      (footprint "easyedapro:R0402")
      (description "电阻类型:厚膜电阻;阻值:10kΩ;精度:±1%;功率:62.5mW;最大工作电压:50V;温度系数:±100ppm/°C;")
      (fields (field (name "Manufacturer Part") "RC0402FR-0710KL") (field (name "Manufacturer") "YAGEO(国巨)"))
      (libsource (lib "easyedapro") (part "RC0402FR-0710KL"))
    )
    (comp (ref "R14")
      (value "10kΩ")
      (footprint "easyedapro:R0402")
      (description "电阻类型:厚膜电阻;阻值:10kΩ;精度:±1%;功率:62.5mW;最大工作电压:50V;温度系数:±100ppm/°C;")
      (fields (field (name "Manufacturer Part") "RC0402FR-0710KL") (field (name "Manufacturer") "YAGEO(国巨)"))
      (libsource (lib "easyedapro") (part "RC0402FR-0710KL"))
    )
    (comp (ref "R15")
      (value "1.5kΩ")
      (footprint "easyedapro:R0402")
      (description "电阻类型:厚膜电阻;阻值:1.5kΩ;精度:±1%;功率:62.5mW;最大工作电压:50V;温度系数:±100ppm/°C;")
      (fields
        (field (name "Manufacturer Part") "0402WGF1501TCE")
        (field (name "Manufacturer") "UNI-ROYAL(厚声)")
      )
      (libsource (lib "easyedapro") (part "0402WGF1501TCE"))
    )
    (comp (ref "R16")
      (value "100Ω")
      (footprint "easyedapro:R0402")
      (description "电阻类型:厚膜电阻;阻值:100Ω;精度:±1%;功率:62.5mW;最大工作电压:50V;温度系数:±200ppm/°C;")
      (fields
        (field (name "Manufacturer Part") "0402WGF1000TCE")
        (field (name "Manufacturer") "UNI-ROYAL(厚声)")
      )
      (libsource (lib "easyedapro") (part "0402WGF1000TCE"))
    )
    (comp (ref "R17")
      (value "5.1kΩ")
      (footprint "easyedapro:R0402")
      (description "阻值:5.1kΩ;精度:±1%;功率:62.5mW;温度系数:±100ppm/°C;电阻类型:厚膜电阻;")
      (fields
        (field (name "Manufacturer Part") "0402WGF5101TCE")
        (field (name "Manufacturer") "UNI-ROYAL(厚声)")
      )
      (libsource (lib "easyedapro") (part "0402WGF5101TCE"))
    )
    (comp (ref "U4")
      (value "AIR32F103CCT6-LQFP48")
      (footprint "easyedapro:LQFP-48_L7.0-W7.0-P0.50-LS9.0-BL")
      (libsource (lib "easyedapro") (part "AIR32F103CBT6-LQFP48"))
    )
    (comp (ref "X2")
      (value "8MHz")
      (footprint "easyedapro:OSC-SMD_4P-L3.2-W2.5-BL")
      (description "晶振类型:贴片晶振;频率:8MHz;常温频差:±10ppm;外接负载电容:12pF;频率稳定度(全温):±30ppm;")
      (fields (field (name "Manufacturer Part") "X32258MOB4SI") (field (name "Manufacturer") "YXC(扬兴晶振)"))
      (libsource (lib "easyedapro") (part "X32258MOB4SI"))
    )
    (comp (ref "C1")
      (value "10uF")
      (footprint "easyedapro:C0402")
      (description "容值:10uF;精度:±20%;额定电压:6.3V;材质(温度系数):X5R;")
      (fields
        (field (name "Manufacturer Part") "CL05A106MQ5NUNC")
        (field (name "Manufacturer") "SAMSUNG(三星)")
      )
      (libsource (lib "easyedapro") (part "CL05A106MQ5NUNC"))
    )
    (comp (ref "C2")
      (value "100nF")
      (footprint "easyedapro:C0402")
      (description "容值:100nF;精度:±10%;额定电压:16V;材质(温度系数):X7R;")
      (fields
        (field (name "Manufacturer Part") "CC0402KRX7R7BB104")
        (field (name "Manufacturer") "YAGEO(国巨)")
      )
      (libsource (lib "easyedapro") (part "CC0402KRX7R7BB104"))
    )
    (comp (ref "C9")
      (value "12pF")
      (footprint "easyedapro:C0402")
      (description "容值:12pF;精度:±5%;额定电压:50V;材质(温度系数):C0G;")
      (fields (field (name "Manufacturer Part") "0402CG120J500NT") (field (name "Manufacturer") "FH(风华)"))
      (libsource (lib "easyedapro") (part "0402CG120J500NT"))
    )
    (comp (ref "C10")
      (value "12pF")
      (footprint "easyedapro:C0402")
      (description "容值:12pF;精度:±5%;额定电压:50V;材质(温度系数):C0G;")
      (fields (field (name "Manufacturer Part") "0402CG120J500NT") (field (name "Manufacturer") "FH(风华)"))
      (libsource (lib "easyedapro") (part "0402CG120J500NT"))
    )
    (comp (ref "C11")
      (value "100nF")
      (footprint "easyedapro:C0402")
      (description "容值:100nF;精度:±10%;额定电压:16V;材质(温度系数):X7R;")
      (fields
        (field (name "Manufacturer Part") "CC0402KRX7R7BB104")
        (field (name "Manufacturer") "YAGEO(国巨)")
      )
      (libsource (lib "easyedapro") (part "CC0402KRX7R7BB104"))
    )
    (comp (ref "CN2")
      (value "顶板接口")
      (footprint "easyedapro:CONN-TH_12P-P2.00_HCTL_HC-PHD")
      (fields (field (name "Manufacturer Part") "HC-PHD-2*6A") (field (name "Manufacturer") "HCTL(华灿天禄)"))
      (libsource (lib "easyedapro") (part "HC-PHD-2*6A"))
    )
    (comp (ref "LED2")
      (value "Run LED")
      (footprint "easyedapro:LED0603-RD_RED")
      (fields (field (name "Manufacturer Part") "NCD0603R1") (field (name "Manufacturer") "国星光电"))
      (libsource (lib "easyedapro") (part "FC-DA1608HRK-620D"))
    )
    (comp (ref "R3")
      (value "10kΩ")
      (footprint "easyedapro:R0402")
      (description "电阻类型:厚膜电阻;阻值:10kΩ;精度:±1%;功率:62.5mW;最大工作电压:50V;温度系数:±100ppm/°C;")
      (fields (field (name "Manufacturer Part") "RC0402FR-0710KL") (field (name "Manufacturer") "YAGEO(国巨)"))
      (libsource (lib "easyedapro") (part "RC0402FR-0710KL"))
    )
    (comp (ref "R6")
      (value "1.5kΩ")
      (footprint "easyedapro:R0402")
      (description "电阻类型:厚膜电阻;阻值:1.5kΩ;精度:±1%;功率:62.5mW;最大工作电压:50V;温度系数:±100ppm/°C;")
      (fields
        (field (name "Manufacturer Part") "0402WGF1501TCE")
        (field (name "Manufacturer") "UNI-ROYAL(厚声)")
      )
      (libsource (lib "easyedapro") (part "0402WGF1501TCE"))
    )
    (comp (ref "R7")
      (value "10kΩ")
      (footprint "easyedapro:R0402")
      (description "电阻类型:厚膜电阻;阻值:10kΩ;精度:±1%;功率:62.5mW;最大工作电压:50V;温度系数:±100ppm/°C;")
      (fields (field (name "Manufacturer Part") "RC0402FR-0710KL") (field (name "Manufacturer") "YAGEO(国巨)"))
      (libsource (lib "easyedapro") (part "RC0402FR-0710KL"))
    )
    (comp (ref "R8")
      (value "10kΩ")
      (footprint "easyedapro:R0402")
      (description "电阻类型:厚膜电阻;阻值:10kΩ;精度:±1%;功率:62.5mW;最大工作电压:50V;温度系数:±100ppm/°C;")
      (fields (field (name "Manufacturer Part") "RC0402FR-0710KL") (field (name "Manufacturer") "YAGEO(国巨)"))
      (libsource (lib "easyedapro") (part "RC0402FR-0710KL"))
    )
    (comp (ref "R18")
      (value "5.1kΩ")
      (footprint "easyedapro:R0402")
      (description "阻值:5.1kΩ;精度:±1%;功率:62.5mW;温度系数:±100ppm/°C;电阻类型:厚膜电阻;")
      (fields
        (field (name "Manufacturer Part") "0402WGF5101TCE")
        (field (name "Manufacturer") "UNI-ROYAL(厚声)")
      )
      (libsource (lib "easyedapro") (part "0402WGF5101TCE"))
    )
    (comp (ref "R36")
      (value "68kΩ")
      (footprint "easyedapro:R0402")
      (description "阻值:68kΩ;精度:±1%;功率:62.5mW;温度系数:±100ppm/°C;电阻类型:厚膜电阻;")
      (fields
        (field (name "Manufacturer Part") "0402WGF6802TCE")
        (field (name "Manufacturer") "UNI-ROYAL(厚声)")
      )
      (libsource (lib "easyedapro") (part "0402WGF6802TCE"))
    )
    (comp (ref "R37")
      (value "10kΩ")
      (footprint "easyedapro:R0402")
      (description "电阻类型:厚膜电阻;阻值:10kΩ;精度:±1%;功率:62.5mW;最大工作电压:50V;温度系数:±100ppm/°C;")
      (fields (field (name "Manufacturer Part") "RC0402FR-0710KL") (field (name "Manufacturer") "YAGEO(国巨)"))
      (libsource (lib "easyedapro") (part "RC0402FR-0710KL"))
    )
    (comp (ref "R38")
      (value "10kΩ")
      (footprint "easyedapro:R0402")
      (description "电阻类型:厚膜电阻;阻值:10kΩ;精度:±1%;功率:62.5mW;最大工作电压:50V;温度系数:±100ppm/°C;")
      (fields (field (name "Manufacturer Part") "RC0402FR-0710KL") (field (name "Manufacturer") "YAGEO(国巨)"))
      (libsource (lib "easyedapro") (part "RC0402FR-0710KL"))
    )
    (comp (ref "U2")
      (value "AIR32F103CCT6-LQFP48")
      (footprint "easyedapro:LQFP-48_L7.0-W7.0-P0.50-LS9.0-BL")
      (libsource (lib "easyedapro") (part "AIR32F103CBT6-LQFP48"))
    )
    (comp (ref "U9")
      (value "AHT20")
      (footprint "easyedapro:SENSOR-SMD_L3.0-W3.0-P1.00-BR")
      (fields (field (name "Manufacturer") "广州奥松"))
      (libsource (lib "easyedapro") (part "AHT20_C2757850"))
    )
    (comp (ref "X3")
      (value "8MHz")
      (footprint "easyedapro:OSC-SMD_4P-L3.2-W2.5-BL")
      (description "晶振类型:贴片晶振;频率:8MHz;常温频差:±10ppm;外接负载电容:12pF;频率稳定度(全温):±30ppm;")
      (fields (field (name "Manufacturer Part") "X32258MOB4SI") (field (name "Manufacturer") "YXC(扬兴晶振)"))
      (libsource (lib "easyedapro") (part "X32258MOB4SI"))
    )
    (comp (ref "CN1")
      (value "DB2ERC-3.81-2P-GN")
      (footprint "easyedapro:CONN-TH_2P-P3.81_DB2ERC-3.81-2P")
      (fields (field (name "Manufacturer") "DORABO(地博电气)"))
      (libsource (lib "easyedapro") (part "DB2ERC-3.81-2P"))
    )
    (comp (ref "H2")
      (value "PZ254V-11-06P")
      (footprint "easyedapro:HDR-TH_6P-P2.54-V-M")
      (fields (field (name "Manufacturer") "XFCN(兴飞)"))
      (libsource (lib "easyedapro") (part "PZ254V-11-06P"))
    )
    (comp (ref "R19")
      (value "1.5kΩ")
      (footprint "easyedapro:R0402")
      (description "电阻类型:厚膜电阻;阻值:1.5kΩ;精度:±1%;功率:62.5mW;最大工作电压:50V;温度系数:±100ppm/°C;")
      (fields
        (field (name "Manufacturer Part") "0402WGF1501TCE")
        (field (name "Manufacturer") "UNI-ROYAL(厚声)")
      )
      (libsource (lib "easyedapro") (part "0402WGF1501TCE"))
    )
    (comp (ref "R20")
      (value "10kΩ")
      (footprint "easyedapro:R0402")
      (description "电阻类型:厚膜电阻;阻值:10kΩ;精度:±1%;功率:62.5mW;最大工作电压:50V;温度系数:±100ppm/°C;")
      (fields (field (name "Manufacturer Part") "RC0402FR-0710KL") (field (name "Manufacturer") "YAGEO(国巨)"))
      (libsource (lib "easyedapro") (part "RC0402FR-0710KL"))
    )
    (comp (ref "R21")
      (value "10kΩ")
      (footprint "easyedapro:R0402")
      (description "电阻类型:厚膜电阻;阻值:10kΩ;精度:±1%;功率:62.5mW;最大工作电压:50V;温度系数:±100ppm/°C;")
      (fields (field (name "Manufacturer Part") "RC0402FR-0710KL") (field (name "Manufacturer") "YAGEO(国巨)"))
      (libsource (lib "easyedapro") (part "RC0402FR-0710KL"))
    )
    (comp (ref "R22")
      (value "1.5kΩ")
      (footprint "easyedapro:R0402")
      (description "电阻类型:厚膜电阻;阻值:1.5kΩ;精度:±1%;功率:62.5mW;最大工作电压:50V;温度系数:±100ppm/°C;")
      (fields
        (field (name "Manufacturer Part") "0402WGF1501TCE")
        (field (name "Manufacturer") "UNI-ROYAL(厚声)")
      )
      (libsource (lib "easyedapro") (part "0402WGF1501TCE"))
    )
    (comp (ref "R23")
      (value "1.5kΩ")
      (footprint "easyedapro:R0402")
      (description "电阻类型:厚膜电阻;阻值:1.5kΩ;精度:±1%;功率:62.5mW;最大工作电压:50V;温度系数:±100ppm/°C;")
      (fields
        (field (name "Manufacturer Part") "0402WGF1501TCE")
        (field (name "Manufacturer") "UNI-ROYAL(厚声)")
      )
      (libsource (lib "easyedapro") (part "0402WGF1501TCE"))
    )
    (comp (ref "R24")
      (value "1.5kΩ")
      (footprint "easyedapro:R0402")
      (description "电阻类型:厚膜电阻;阻值:1.5kΩ;精度:±1%;功率:62.5mW;最大工作电压:50V;温度系数:±100ppm/°C;")
      (fields
        (field (name "Manufacturer Part") "0402WGF1501TCE")
        (field (name "Manufacturer") "UNI-ROYAL(厚声)")
      )
      (libsource (lib "easyedapro") (part "0402WGF1501TCE"))
    )
    (comp (ref "R25")
      (value "100Ω")
      (footprint "easyedapro:R0402")
      (description "电阻类型:厚膜电阻;阻值:100Ω;精度:±1%;功率:62.5mW;最大工作电压:50V;温度系数:±200ppm/°C;")
      (fields
        (field (name "Manufacturer Part") "0402WGF1000TCE")
        (field (name "Manufacturer") "UNI-ROYAL(厚声)")
      )
      (libsource (lib "easyedapro") (part "0402WGF1000TCE"))
    )
    (comp (ref "R26")
      (value "100Ω")
      (footprint "easyedapro:R0402")
      (description "电阻类型:厚膜电阻;阻值:100Ω;精度:±1%;功率:62.5mW;最大工作电压:50V;温度系数:±200ppm/°C;")
      (fields
        (field (name "Manufacturer Part") "0402WGF1000TCE")
        (field (name "Manufacturer") "UNI-ROYAL(厚声)")
      )
      (libsource (lib "easyedapro") (part "0402WGF1000TCE"))
    )
    (comp (ref "R27")
      (value "100Ω")
      (footprint "easyedapro:R0402")
      (description "电阻类型:厚膜电阻;阻值:100Ω;精度:±1%;功率:62.5mW;最大工作电压:50V;温度系数:±200ppm/°C;")
      (fields
        (field (name "Manufacturer Part") "0402WGF1000TCE")
        (field (name "Manufacturer") "UNI-ROYAL(厚声)")
      )
      (libsource (lib "easyedapro") (part "0402WGF1000TCE"))
    )
    (comp (ref "R28")
      (value "100Ω")
      (footprint "easyedapro:R0402")
      (description "电阻类型:厚膜电阻;阻值:100Ω;精度:±1%;功率:62.5mW;最大工作电压:50V;温度系数:±200ppm/°C;")
      (fields
        (field (name "Manufacturer Part") "0402WGF1000TCE")
        (field (name "Manufacturer") "UNI-ROYAL(厚声)")
      )
      (libsource (lib "easyedapro") (part "0402WGF1000TCE"))
    )
    (comp (ref "R29")
      (value "100Ω")
      (footprint "easyedapro:R0402")
      (description "电阻类型:厚膜电阻;阻值:100Ω;精度:±1%;功率:62.5mW;最大工作电压:50V;温度系数:±200ppm/°C;")
      (fields
        (field (name "Manufacturer Part") "0402WGF1000TCE")
        (field (name "Manufacturer") "UNI-ROYAL(厚声)")
      )
      (libsource (lib "easyedapro") (part "0402WGF1000TCE"))
    )
    (comp (ref "R30")
      (value "100Ω")
      (footprint "easyedapro:R0402")
      (description "电阻类型:厚膜电阻;阻值:100Ω;精度:±1%;功率:62.5mW;最大工作电压:50V;温度系数:±200ppm/°C;")
      (fields
        (field (name "Manufacturer Part") "0402WGF1000TCE")
        (field (name "Manufacturer") "UNI-ROYAL(厚声)")
      )
      (libsource (lib "easyedapro") (part "0402WGF1000TCE"))
    )
    (comp (ref "R31")
      (value "100Ω")
      (footprint "easyedapro:R0402")
      (description "电阻类型:厚膜电阻;阻值:100Ω;精度:±1%;功率:62.5mW;最大工作电压:50V;温度系数:±200ppm/°C;")
      (fields
        (field (name "Manufacturer Part") "0402WGF1000TCE")
        (field (name "Manufacturer") "UNI-ROYAL(厚声)")
      )
      (libsource (lib "easyedapro") (part "0402WGF1000TCE"))
    )
    (comp (ref "R32")
      (value "100Ω")
      (footprint "easyedapro:R0402")
      (description "电阻类型:厚膜电阻;阻值:100Ω;精度:±1%;功率:62.5mW;最大工作电压:50V;温度系数:±200ppm/°C;")
      (fields
        (field (name "Manufacturer Part") "0402WGF1000TCE")
        (field (name "Manufacturer") "UNI-ROYAL(厚声)")
      )
      (libsource (lib "easyedapro") (part "0402WGF1000TCE"))
    )
    (comp (ref "R33")
      (value "100Ω")
      (footprint "easyedapro:R0402")
      (description "电阻类型:厚膜电阻;阻值:100Ω;精度:±1%;功率:62.5mW;最大工作电压:50V;温度系数:±200ppm/°C;")
      (fields
        (field (name "Manufacturer Part") "0402WGF1000TCE")
        (field (name "Manufacturer") "UNI-ROYAL(厚声)")
      )
      (libsource (lib "easyedapro") (part "0402WGF1000TCE"))
    )
    (comp (ref "R34")
      (value "0Ω")
      (footprint "easyedapro:R1206")
      (description "电阻类型:厚膜电阻;阻值:0Ω;精度:±1%;功率:250mW;最大工作电压:200V;温度系数:±800ppm/°C;")
      (fields
        (field (name "Manufacturer Part") "1206W4F0000T5E")
        (field (name "Manufacturer") "UNI-ROYAL(厚声)")
      )
      (libsource (lib "easyedapro") (part "1206W4F0000T5E"))
    )
    (comp (ref "R35")
      (value "0Ω")
      (footprint "easyedapro:R1206")
      (description "电阻类型:厚膜电阻;阻值:0Ω;精度:±1%;功率:250mW;最大工作电压:200V;温度系数:±800ppm/°C;")
      (fields
        (field (name "Manufacturer Part") "1206W4F0000T5E")
        (field (name "Manufacturer") "UNI-ROYAL(厚声)")
      )
      (libsource (lib "easyedapro") (part "1206W4F0000T5E"))
    )
    (comp (ref "U5")
      (value "MAX3485ESA")
      (footprint "easyedapro:SOP-8_L5.0-W4.0-P1.27-LS6.0-BL")
      (description "类型:收发器;数据速率:12Mbps;驱动器/接收器:1/1;")
      (fields (field (name "Manufacturer") "UMW(友台半导体)"))
      (libsource (lib "easyedapro") (part "MAX3485ESA"))
    )
    (comp (ref "U6")
      (value "MPCM601(T1)-GV")
      (footprint "easyedapro:SOP-5-L4.4-W3.6-P1.27-LS7.0-TL")
      (description "输入类型:DC;电源电压:4.5V~5.5V；2.7V~3.6V;共模瞬变抗扰度CMTI:10kV/us;数据速率:15Mbit/s;传播延迟tpLH/tpHL:75ns；90ns;")
      (fields (field (name "Manufacturer") "MTC(美禄)"))
      (libsource (lib "easyedapro") (part "MPCM601(T1)-GV"))
    )
    (comp (ref "U7")
      (value "MPCM601(T1)-GV")
      (footprint "easyedapro:SOP-5-L4.4-W3.6-P1.27-LS7.0-TL")
      (description "输入类型:DC;电源电压:4.5V~5.5V；2.7V~3.6V;共模瞬变抗扰度CMTI:10kV/us;数据速率:15Mbit/s;传播延迟tpLH/tpHL:75ns；90ns;")
      (fields (field (name "Manufacturer") "MTC(美禄)"))
      (libsource (lib "easyedapro") (part "MPCM601(T1)-GV"))
    )
    (comp (ref "U8")
      (value "MPCM601(T1)-GV")
      (footprint "easyedapro:SOP-5-L4.4-W3.6-P1.27-LS7.0-TL")
      (description "输入类型:DC;电源电压:4.5V~5.5V；2.7V~3.6V;共模瞬变抗扰度CMTI:10kV/us;数据速率:15Mbit/s;传播延迟tpLH/tpHL:75ns；90ns;")
      (fields (field (name "Manufacturer") "MTC(美禄)"))
      (libsource (lib "easyedapro") (part "MPCM601(T1)-GV"))
    )
  )
  (nets
    (net (code "1") (name "3V3") (class "Default")
      (node (ref "C1") (pin "2") (pinfunction "2_2") (pintype "input"))
      (node (ref "C16") (pin "2") (pinfunction "2_2") (pintype "input"))
      (node (ref "C17") (pin "2") (pinfunction "2_2") (pintype "unspecified"))
      (node (ref "C2") (pin "2") (pinfunction "2_2") (pintype "unspecified"))
      (node (ref "C30") (pin "2") (pinfunction "2_2") (pintype "input"))
      (node (ref "C31") (pin "2") (pinfunction "2_2") (pintype "unspecified"))
      (node (ref "CN2") (pin "2") (pinfunction "2_2") (pintype "unspecified"))
      (node (ref "H1") (pin "1") (pinfunction "1_1") (pintype "unspecified"))
      (node (ref "H2") (pin "4") (pinfunction "4_4") (pintype "unspecified"))
      (node (ref "L1") (pin "2") (pinfunction "2_2") (pintype "input"))
      (node (ref "R12") (pin "1") (pinfunction "1_1") (pintype "input"))
      (node (ref "R15") (pin "2") (pinfunction "2_2") (pintype "input"))
      (node (ref "R24") (pin "1") (pinfunction "1_1") (pintype "input"))
      (node (ref "R35") (pin "1") (pinfunction "1_1") (pintype "input"))
      (node (ref "R36") (pin "2") (pinfunction "2_2") (pintype "input"))
      (node (ref "R37") (pin "2") (pinfunction "2_2") (pintype "input"))
      (node (ref "R38") (pin "2") (pinfunction "2_2") (pintype "input"))
      (node (ref "R4") (pin "2") (pinfunction "2_2") (pintype "input"))
      (node (ref "R6") (pin "2") (pinfunction "2_2") (pintype "input"))
      (node (ref "R7") (pin "1") (pinfunction "1_1") (pintype "input"))
      (node (ref "R8") (pin "1") (pinfunction "1_1") (pintype "input"))
      (node (ref "U2") (pin "1") (pinfunction "VBAT_1") (pintype "input"))
      (node (ref "U2") (pin "24") (pinfunction "VDD_1_24") (pintype "input"))
      (node (ref "U2") (pin "36") (pinfunction "VDD_2_36") (pintype "input"))
      (node (ref "U2") (pin "48") (pinfunction "VDD_3_48") (pintype "input"))
      (node (ref "U2") (pin "9") (pinfunction "VDDA_9") (pintype "input"))
      (node (ref "U4") (pin "1") (pinfunction "VBAT_1") (pintype "input"))
      (node (ref "U4") (pin "24") (pinfunction "VDD_1_24") (pintype "input"))
      (node (ref "U4") (pin "36") (pinfunction "VDD_2_36") (pintype "input"))
      (node (ref "U4") (pin "48") (pinfunction "VDD_3_48") (pintype "input"))
      (node (ref "U4") (pin "9") (pinfunction "VDDA_9") (pintype "input"))
      (node (ref "U6") (pin "1") (pinfunction "A_1") (pintype "unspecified"))
      (node (ref "U7") (pin "1") (pinfunction "A_1") (pintype "unspecified"))
      (node (ref "U8") (pin "5") (pinfunction "VCC_5") (pintype "unspecified"))
      (node (ref "U9") (pin "2") (pinfunction "VDD_2") (pintype "unspecified"))
    )
    (net (code "2") (name "DAP-CDC") (class "Default")
      (node (ref "U4") (pin "21") (pinfunction "PB10_21") (pintype "input"))
    )
    (net (code "3") (name "DAP-DTR") (class "Default")
      (node (ref "U4") (pin "31") (pinfunction "PA10_31") (pintype "input"))
    )
    (net (code "4") (name "DAP-HID") (class "Default")
      (node (ref "U4") (pin "20") (pinfunction "PB2_20") (pintype "input"))
    )
    (net (code "5") (name "DAP-MSC") (class "Default")
      (node (ref "U4") (pin "22") (pinfunction "PB11_22") (pintype "input"))
    )
    (net (code "6") (name "DAP-NRST") (class "Default")
      (node (ref "C11") (pin "2") (pinfunction "2_2") (pintype "unspecified"))
      (node (ref "R36") (pin "1") (pinfunction "1_1") (pintype "input"))
      (node (ref "U2") (pin "7") (pinfunction "NRST_7") (pintype "input"))
      (node (ref "U4") (pin "18") (pinfunction "PB0_18") (pintype "input"))
    )
    (net (code "7") (name "DAP-RTS") (class "Default")
      (node (ref "U4") (pin "30") (pinfunction "PA9_30") (pintype "input"))
    )
    (net (code "8") (name "DAP-RUN") (class "Default")
      (node (ref "R17") (pin "2") (pinfunction "2_2") (pintype "input"))
      (node (ref "U4") (pin "10") (pinfunction "PA0-WKUP_10") (pintype "input"))
    )
    (net (code "9") (name "DAP-RX") (class "Default")
      (node (ref "R8") (pin "2") (pinfunction "2_2") (pintype "input"))
      (node (ref "U2") (pin "30") (pinfunction "PA9_30") (pintype "input"))
      (node (ref "U4") (pin "13") (pinfunction "PA3_13") (pintype "input"))
    )
    (net (code "10") (name "DAP-SWCLK") (class "Default")
      (node (ref "U2") (pin "37") (pinfunction "PA14_37") (pintype "input"))
      (node (ref "U4") (pin "26") (pinfunction "PB13_26") (pintype "input"))
    )
    (net (code "11") (name "DAP-SWDIO") (class "Default")
      (node (ref "R16") (pin "1") (pinfunction "1_1") (pintype "input"))
      (node (ref "U2") (pin "34") (pinfunction "PA13_34") (pintype "input"))
      (node (ref "U4") (pin "25") (pinfunction "PB12_25") (pintype "input"))
    )
    (net (code "12") (name "DAP-TX") (class "Default")
      (node (ref "R7") (pin "2") (pinfunction "2_2") (pintype "input"))
      (node (ref "U2") (pin "31") (pinfunction "PA10_31") (pintype "input"))
      (node (ref "U4") (pin "12") (pinfunction "PA2_12") (pintype "input"))
    )
    (net (code "13") (name "DAPLINK-B0") (class "Default")
      (node (ref "H1") (pin "5") (pinfunction "5_5") (pintype "unspecified"))
      (node (ref "R14") (pin "1") (pinfunction "1_1") (pintype "input"))
      (node (ref "U4") (pin "44") (pinfunction "BOOT0_44") (pintype "input"))
    )
    (net (code "14") (name "DAPLINK-NRST") (class "Default")
      (node (ref "C24") (pin "2") (pinfunction "2_2") (pintype "unspecified"))
      (node (ref "H1") (pin "6") (pinfunction "6_6") (pintype "unspecified"))
      (node (ref "R4") (pin "1") (pinfunction "1_1") (pintype "input"))
      (node (ref "U4") (pin "7") (pinfunction "NRST_7") (pintype "input"))
    )
    (net (code "15") (name "DAPLINK-SWCLK") (class "Default")
      (node (ref "H1") (pin "3") (pinfunction "3_3") (pintype "unspecified"))
      (node (ref "U4") (pin "37") (pinfunction "PA14_37") (pintype "input"))
    )
    (net (code "16") (name "DAPLINK-SWDIO") (class "Default")
      (node (ref "H1") (pin "2") (pinfunction "2_2") (pintype "unspecified"))
      (node (ref "U4") (pin "34") (pinfunction "PA13_34") (pintype "input"))
    )
    (net (code "17") (name "DM-UP") (class "Default")
      (node (ref "U1") (pin "10") (pinfunction "DMU_10") (pintype "unspecified"))
      (node (ref "USB1") (pin "5") (pinfunction "DN2_5") (pintype "unspecified"))
      (node (ref "USB1") (pin "7") (pinfunction "DN1_7") (pintype "unspecified"))
    )
    (net (code "18") (name "DM1") (class "Default")
      (node (ref "U1") (pin "7") (pinfunction "DM1_7") (pintype "unspecified"))
      (node (ref "U4") (pin "32") (pinfunction "PA11_32") (pintype "input"))
    )
    (net (code "19") (name "DM2") (class "Default")
      (node (ref "U1") (pin "5") (pinfunction "DM2_5") (pintype "unspecified"))
      (node (ref "U2") (pin "32") (pinfunction "PA11_32") (pintype "input"))
    )
    (net (code "20") (name "DM3") (class "Default")
      (node (ref "U1") (pin "3") (pinfunction "DM3_3") (pintype "unspecified"))
      (node (ref "USB3") (pin "2") (pinfunction "D-_2") (pintype "unspecified"))
    )
    (net (code "21") (name "DM4") (class "Default")
      (node (ref "U1") (pin "1") (pinfunction "DM4_1") (pintype "unspecified"))
      (node (ref "USB2") (pin "2") (pinfunction "D-_2") (pintype "unspecified"))
    )
    (net (code "22") (name "DP-UP") (class "Default")
      (node (ref "U1") (pin "11") (pinfunction "DPU_11") (pintype "unspecified"))
      (node (ref "USB1") (pin "6") (pinfunction "DP1_6") (pintype "unspecified"))
      (node (ref "USB1") (pin "8") (pinfunction "DP2_8") (pintype "unspecified"))
    )
    (net (code "23") (name "DP1") (class "Default")
      (node (ref "R15") (pin "1") (pinfunction "1_1") (pintype "input"))
      (node (ref "U1") (pin "8") (pinfunction "DP1_8") (pintype "unspecified"))
      (node (ref "U4") (pin "33") (pinfunction "PA12_33") (pintype "input"))
    )
    (net (code "24") (name "DP2") (class "Default")
      (node (ref "R6") (pin "1") (pinfunction "1_1") (pintype "input"))
      (node (ref "U1") (pin "6") (pinfunction "DP2_6") (pintype "unspecified"))
      (node (ref "U2") (pin "33") (pinfunction "PA12_33") (pintype "input"))
    )
    (net (code "25") (name "DP3") (class "Default")
      (node (ref "U1") (pin "4") (pinfunction "DP3_4") (pintype "unspecified"))
      (node (ref "USB3") (pin "3") (pinfunction "D+_3") (pintype "unspecified"))
    )
    (net (code "26") (name "DP4") (class "Default")
      (node (ref "U1") (pin "2") (pinfunction "DP4_2") (pintype "unspecified"))
      (node (ref "USB2") (pin "3") (pinfunction "D+_3") (pintype "unspecified"))
    )
    (net (code "27") (name "GND") (class "Default")
      (node (ref "C1") (pin "1") (pinfunction "1_1") (pintype "input"))
      (node (ref "C10") (pin "1") (pinfunction "1_1") (pintype "input"))
      (node (ref "C11") (pin "1") (pinfunction "1_1") (pintype "unspecified"))
      (node (ref "C15") (pin "1") (pinfunction "1_1") (pintype "input"))
      (node (ref "C16") (pin "1") (pinfunction "1_1") (pintype "input"))
      (node (ref "C17") (pin "1") (pinfunction "1_1") (pintype "unspecified"))
      (node (ref "C2") (pin "1") (pinfunction "1_1") (pintype "unspecified"))
      (node (ref "C22") (pin "2") (pinfunction "2_2") (pintype "input"))
      (node (ref "C23") (pin "2") (pinfunction "2_2") (pintype "input"))
      (node (ref "C24") (pin "1") (pinfunction "1_1") (pintype "unspecified"))
      (node (ref "C25") (pin "1") (pinfunction "1_1") (pintype "input"))
      (node (ref "C26") (pin "1") (pinfunction "1_1") (pintype "input"))
      (node (ref "C3") (pin "1") (pinfunction "1_1") (pintype "unspecified"))
      (node (ref "C30") (pin "1") (pinfunction "1_1") (pintype "input"))
      (node (ref "C31") (pin "1") (pinfunction "1_1") (pintype "unspecified"))
      (node (ref "C4") (pin "1") (pinfunction "1_1") (pintype "input"))
      (node (ref "C5") (pin "1") (pinfunction "1_1") (pintype "input"))
      (node (ref "C6") (pin "1") (pinfunction "1_1") (pintype "unspecified"))
      (node (ref "C7") (pin "1") (pinfunction "1_1") (pintype "input"))
      (node (ref "C8") (pin "2") (pinfunction "2_2") (pintype "input"))
      (node (ref "C9") (pin "1") (pinfunction "1_1") (pintype "input"))
      (node (ref "CN2") (pin "1") (pinfunction "1_1") (pintype "unspecified"))
      (node (ref "CN2") (pin "7") (pinfunction "7_7") (pintype "unspecified"))
      (node (ref "H1") (pin "4") (pinfunction "4_4") (pintype "unspecified"))
      (node (ref "H2") (pin "6") (pinfunction "6_6") (pintype "unspecified"))
      (node (ref "LED1") (pin "1") (pinfunction "K_1") (pintype "input"))
      (node (ref "LED2") (pin "1") (pinfunction "K_1") (pintype "input"))
      (node (ref "R1") (pin "2") (pinfunction "2_2") (pintype "input"))
      (node (ref "R13") (pin "2") (pinfunction "2_2") (pintype "input"))
      (node (ref "R14") (pin "2") (pinfunction "2_2") (pintype "input"))
      (node (ref "R2") (pin "2") (pinfunction "2_2") (pintype "input"))
      (node (ref "R3") (pin "2") (pinfunction "2_2") (pintype "input"))
      (node (ref "R34") (pin "2") (pinfunction "2_2") (pintype "input"))
      (node (ref "U1") (pin "14") (pinfunction "GND_14") (pintype "unspecified"))
      (node (ref "U2") (pin "23") (pinfunction "VSS_1_23") (pintype "input"))
      (node (ref "U2") (pin "35") (pinfunction "VSS_2_35") (pintype "input"))
      (node (ref "U2") (pin "47") (pinfunction "VSS_3_47") (pintype "input"))
      (node (ref "U2") (pin "8") (pinfunction "VSSA_8") (pintype "input"))
      (node (ref "U3") (pin "2") (pinfunction "GND_2") (pintype "input"))
      (node (ref "U4") (pin "23") (pinfunction "VSS_1_23") (pintype "input"))
      (node (ref "U4") (pin "35") (pinfunction "VSS_2_35") (pintype "input"))
      (node (ref "U4") (pin "47") (pinfunction "VSS_3_47") (pintype "input"))
      (node (ref "U4") (pin "8") (pinfunction "VSSA_8") (pintype "input"))
      (node (ref "U8") (pin "3") (pinfunction "GND_3") (pintype "unspecified"))
      (node (ref "U9") (pin "5") (pinfunction "GND_5") (pintype "unspecified"))
      (node (ref "USB1") (pin "1") (pinfunction "GND_1") (pintype "unspecified"))
      (node (ref "USB1") (pin "12") (pinfunction "GND_12") (pintype "unspecified"))
      (node (ref "USB1") (pin "13") (pinfunction "SHELL_13") (pintype "unspecified"))
      (node (ref "USB1") (pin "14") (pinfunction "SHELL_14") (pintype "unspecified"))
      (node (ref "USB2") (pin "4") (pinfunction "GND_4") (pintype "unspecified"))
      (node (ref "USB2") (pin "5") (pinfunction "SH1_5") (pintype "unspecified"))
      (node (ref "USB2") (pin "6") (pinfunction "SH2_6") (pintype "unspecified"))
      (node (ref "USB3") (pin "4") (pinfunction "GND_4") (pintype "unspecified"))
      (node (ref "USB3") (pin "5") (pinfunction "SH1_5") (pintype "unspecified"))
      (node (ref "USB3") (pin "6") (pinfunction "SH2_6") (pintype "unspecified"))
      (node (ref "X1") (pin "2") (pinfunction "GND_2") (pintype "unspecified"))
      (node (ref "X1") (pin "4") (pinfunction "GND_4") (pintype "unspecified"))
      (node (ref "X2") (pin "2") (pinfunction "GND_2") (pintype "input"))
      (node (ref "X2") (pin "4") (pinfunction "GND_4") (pintype "input"))
      (node (ref "X3") (pin "2") (pinfunction "GND_2") (pintype "input"))
      (node (ref "X3") (pin "4") (pinfunction "GND_4") (pintype "input"))
    )
    (net (code "28") (name "I2C-SCL") (class "Default")
      (node (ref "CN2") (pin "3") (pinfunction "3_3") (pintype "unspecified"))
      (node (ref "R37") (pin "1") (pinfunction "1_1") (pintype "input"))
      (node (ref "U2") (pin "45") (pinfunction "PB8_45") (pintype "input"))
      (node (ref "U9") (pin "3") (pinfunction "SCL_3") (pintype "unspecified"))
    )
    (net (code "29") (name "I2C-SDA") (class "Default")
      (node (ref "CN2") (pin "4") (pinfunction "4_4") (pintype "unspecified"))
      (node (ref "R38") (pin "1") (pinfunction "1_1") (pintype "input"))
      (node (ref "U2") (pin "46") (pinfunction "PB9_46") (pintype "input"))
      (node (ref "U9") (pin "4") (pinfunction "SDA_4") (pintype "unspecified"))
    )
    (net (code "30") (name "Net-(LED1-A)") (class "Default")
      (node (ref "LED1") (pin "2") (pinfunction "A_2") (pintype "input"))
      (node (ref "R17") (pin "1") (pinfunction "1_1") (pintype "input"))
    )
    (net (code "31") (name "Net-(LED2-A)") (class "Default")
      (node (ref "LED2") (pin "2") (pinfunction "A_2") (pintype "input"))
      (node (ref "R18") (pin "1") (pinfunction "1_1") (pintype "input"))
    )
    (net (code "32") (name "Net-(R25-Pad1)") (class "Default")
      (node (ref "R25") (pin "1") (pinfunction "1_1") (pintype "input"))
      (node (ref "R26") (pin "1") (pinfunction "1_1") (pintype "input"))
    )
    (net (code "33") (name "Net-(R26-Pad2)") (class "Default")
      (node (ref "R26") (pin "2") (pinfunction "2_2") (pintype "input"))
      (node (ref "R27") (pin "2") (pinfunction "2_2") (pintype "input"))
    )
    (net (code "34") (name "Net-(R28-Pad1)") (class "Default")
      (node (ref "R28") (pin "1") (pinfunction "1_1") (pintype "input"))
      (node (ref "R29") (pin "1") (pinfunction "1_1") (pintype "input"))
    )
    (net (code "35") (name "Net-(R29-Pad2)") (class "Default")
      (node (ref "R29") (pin "2") (pinfunction "2_2") (pintype "input"))
      (node (ref "R30") (pin "2") (pinfunction "2_2") (pintype "input"))
    )
    (net (code "36") (name "Net-(R31-Pad1)") (class "Default")
      (node (ref "R31") (pin "1") (pinfunction "1_1") (pintype "input"))
      (node (ref "R32") (pin "1") (pinfunction "1_1") (pintype "input"))
    )
    (net (code "37") (name "Net-(R32-Pad2)") (class "Default")
      (node (ref "R32") (pin "2") (pinfunction "2_2") (pintype "input"))
      (node (ref "R33") (pin "2") (pinfunction "2_2") (pintype "input"))
    )
    (net (code "38") (name "Net-(U1-VDD33)") (class "Default")
      (node (ref "C3") (pin "2") (pinfunction "2_2") (pintype "unspecified"))
      (node (ref "C4") (pin "2") (pinfunction "2_2") (pintype "input"))
      (node (ref "U1") (pin "13") (pinfunction "VDD33_13") (pintype "unspecified"))
    )
    (net (code "39") (name "Net-(U1-XI)") (class "Default")
      (node (ref "C7") (pin "2") (pinfunction "2_2") (pintype "input"))
      (node (ref "U1") (pin "16") (pinfunction "XI_16") (pintype "unspecified"))
      (node (ref "X1") (pin "3") (pinfunction "OSC2_3") (pintype "unspecified"))
    )
    (net (code "40") (name "Net-(U1-XO)") (class "Default")
      (node (ref "C8") (pin "1") (pinfunction "1_1") (pintype "input"))
      (node (ref "U1") (pin "15") (pinfunction "XO_15") (pintype "unspecified"))
      (node (ref "X1") (pin "1") (pinfunction "OSC1_1") (pintype "unspecified"))
    )
    (net (code "41") (name "Net-(U2-BOOT0)") (class "Default")
      (node (ref "R3") (pin "1") (pinfunction "1_1") (pintype "input"))
      (node (ref "U2") (pin "44") (pinfunction "BOOT0_44") (pintype "input"))
    )
    (net (code "42") (name "Net-(U2-OSC_IN)") (class "Default")
      (node (ref "C9") (pin "2") (pinfunction "2_2") (pintype "input"))
      (node (ref "U2") (pin "5") (pinfunction "OSC_IN_5") (pintype "input"))
      (node (ref "X3") (pin "3") (pinfunction "3_3") (pintype "input"))
    )
    (net (code "43") (name "Net-(U2-OSC_OUT)") (class "Default")
      (node (ref "C10") (pin "2") (pinfunction "2_2") (pintype "input"))
      (node (ref "U2") (pin "6") (pinfunction "OSC_OUT_6") (pintype "input"))
      (node (ref "X3") (pin "1") (pinfunction "1_1") (pintype "input"))
    )
    (net (code "44") (name "Net-(U2-PA0-WKUP)") (class "Default")
      (node (ref "R18") (pin "2") (pinfunction "2_2") (pintype "input"))
      (node (ref "U2") (pin "10") (pinfunction "PA0-WKUP_10") (pintype "input"))
    )
    (net (code "45") (name "Net-(U3-EN)") (class "Default")
      (node (ref "R11") (pin "1") (pinfunction "1_1") (pintype "input"))
      (node (ref "U3") (pin "1") (pinfunction "EN_1") (pintype "input"))
    )
    (net (code "46") (name "Net-(U3-FB)") (class "Default")
      (node (ref "R12") (pin "2") (pinfunction "2_2") (pintype "input"))
      (node (ref "R13") (pin "1") (pinfunction "1_1") (pintype "input"))
      (node (ref "U3") (pin "5") (pinfunction "FB_5") (pintype "input"))
    )
    (net (code "47") (name "Net-(U3-LX)") (class "Default")
      (node (ref "L1") (pin "1") (pinfunction "1_1") (pintype "input"))
      (node (ref "U3") (pin "3") (pinfunction "LX_3") (pintype "input"))
    )
    (net (code "48") (name "Net-(U4-OSC_IN)") (class "Default")
      (node (ref "C25") (pin "2") (pinfunction "2_2") (pintype "input"))
      (node (ref "U4") (pin "5") (pinfunction "OSC_IN_5") (pintype "input"))
      (node (ref "X2") (pin "3") (pinfunction "3_3") (pintype "input"))
    )
    (net (code "49") (name "Net-(U4-OSC_OUT)") (class "Default")
      (node (ref "C26") (pin "2") (pinfunction "2_2") (pintype "input"))
      (node (ref "U4") (pin "6") (pinfunction "OSC_OUT_6") (pintype "input"))
      (node (ref "X2") (pin "1") (pinfunction "1_1") (pintype "input"))
    )
    (net (code "50") (name "Net-(U4-PB14)") (class "Default")
      (node (ref "R16") (pin "2") (pinfunction "2_2") (pintype "input"))
      (node (ref "U4") (pin "27") (pinfunction "PB14_27") (pintype "input"))
    )
    (net (code "51") (name "Net-(U6-C)") (class "Default")
      (node (ref "R33") (pin "1") (pinfunction "1_1") (pintype "input"))
      (node (ref "U6") (pin "2") (pinfunction "C_2") (pintype "unspecified"))
    )
    (net (code "52") (name "Net-(U7-C)") (class "Default")
      (node (ref "R30") (pin "1") (pinfunction "1_1") (pintype "input"))
      (node (ref "U7") (pin "2") (pinfunction "C_2") (pintype "unspecified"))
    )
    (net (code "53") (name "Net-(U8-C)") (class "Default")
      (node (ref "R25") (pin "2") (pinfunction "2_2") (pintype "input"))
      (node (ref "U8") (pin "2") (pinfunction "C_2") (pintype "unspecified"))
    )
    (net (code "54") (name "Net-(USB1-CC1)") (class "Default")
      (node (ref "R2") (pin "1") (pinfunction "1_1") (pintype "input"))
      (node (ref "USB1") (pin "4") (pinfunction "CC1_4") (pintype "unspecified"))
    )
    (net (code "55") (name "Net-(USB1-CC2)") (class "Default")
      (node (ref "R1") (pin "1") (pinfunction "1_1") (pintype "input"))
      (node (ref "USB1") (pin "10") (pinfunction "CC2_10") (pintype "unspecified"))
    )
    (net (code "56") (name "PB0") (class "Default")
      (node (ref "CN2") (pin "12") (pinfunction "12_12") (pintype "unspecified"))
      (node (ref "U2") (pin "18") (pinfunction "PB0_18") (pintype "input"))
    )
    (net (code "57") (name "PB10") (class "Default")
      (node (ref "CN2") (pin "5") (pinfunction "5_5") (pintype "unspecified"))
      (node (ref "U2") (pin "21") (pinfunction "PB10_21") (pintype "input"))
    )
    (net (code "58") (name "PB11") (class "Default")
      (node (ref "CN2") (pin "6") (pinfunction "6_6") (pintype "unspecified"))
      (node (ref "U2") (pin "22") (pinfunction "PB11_22") (pintype "input"))
    )
    (net (code "59") (name "RS485-A") (class "Default")
      (node (ref "CN1") (pin "1") (pinfunction "1_1") (pintype "unspecified"))
      (node (ref "R19") (pin "2") (pinfunction "2_2") (pintype "input"))
      (node (ref "R20") (pin "1") (pinfunction "1_1") (pintype "input"))
      (node (ref "U5") (pin "6") (pinfunction "A_6") (pintype "unspecified"))
    )
    (net (code "60") (name "RS485-B") (class "Default")
      (node (ref "CN1") (pin "2") (pinfunction "2_2") (pintype "unspecified"))
      (node (ref "R19") (pin "1") (pinfunction "1_1") (pintype "input"))
      (node (ref "R21") (pin "2") (pinfunction "2_2") (pintype "input"))
      (node (ref "U5") (pin "7") (pinfunction "B_7") (pintype "unspecified"))
    )
    (net (code "61") (name "RS485-DE_RE") (class "Default")
      (node (ref "R22") (pin "1") (pinfunction "1_1") (pintype "input"))
      (node (ref "U5") (pin "2") (pinfunction "#RE_2") (pintype "unspecified"))
      (node (ref "U5") (pin "3") (pinfunction "DE_3") (pintype "unspecified"))
      (node (ref "U6") (pin "4") (pinfunction "VO_4") (pintype "unspecified"))
    )
    (net (code "62") (name "RS485-DI") (class "Default")
      (node (ref "R23") (pin "1") (pinfunction "1_1") (pintype "input"))
      (node (ref "U5") (pin "4") (pinfunction "DI_4") (pintype "unspecified"))
      (node (ref "U7") (pin "4") (pinfunction "VO_4") (pintype "unspecified"))
    )
    (net (code "63") (name "RS485-GND") (class "Default")
      (node (ref "H2") (pin "1") (pinfunction "1_1") (pintype "unspecified"))
      (node (ref "R21") (pin "1") (pinfunction "1_1") (pintype "input"))
      (node (ref "R34") (pin "1") (pinfunction "1_1") (pintype "input"))
      (node (ref "U5") (pin "5") (pinfunction "GND_5") (pintype "unspecified"))
      (node (ref "U6") (pin "3") (pinfunction "GND_3") (pintype "unspecified"))
      (node (ref "U7") (pin "3") (pinfunction "GND_3") (pintype "unspecified"))
    )
    (net (code "64") (name "RS485-RO") (class "Default")
      (node (ref "R27") (pin "1") (pinfunction "1_1") (pintype "input"))
      (node (ref "U5") (pin "1") (pinfunction "RO_1") (pintype "unspecified"))
    )
    (net (code "65") (name "RS485-VCC") (class "Default")
      (node (ref "H2") (pin "2") (pinfunction "2_2") (pintype "unspecified"))
      (node (ref "R20") (pin "2") (pinfunction "2_2") (pintype "input"))
      (node (ref "R22") (pin "2") (pinfunction "2_2") (pintype "input"))
      (node (ref "R23") (pin "2") (pinfunction "2_2") (pintype "input"))
      (node (ref "R35") (pin "2") (pinfunction "2_2") (pintype "input"))
      (node (ref "U5") (pin "8") (pinfunction "VCC_8") (pintype "unspecified"))
      (node (ref "U6") (pin "5") (pinfunction "VCC_5") (pintype "unspecified"))
      (node (ref "U7") (pin "5") (pinfunction "VCC_5") (pintype "unspecified"))
      (node (ref "U8") (pin "1") (pinfunction "A_1") (pintype "unspecified"))
    )
    (net (code "66") (name "SPI-CLK") (class "Default")
      (node (ref "CN2") (pin "10") (pinfunction "10_10") (pintype "unspecified"))
      (node (ref "U2") (pin "15") (pinfunction "PA5_15") (pintype "input"))
    )
    (net (code "67") (name "SPI-MISO") (class "Default")
      (node (ref "CN2") (pin "9") (pinfunction "9_9") (pintype "unspecified"))
      (node (ref "U2") (pin "16") (pinfunction "PA6_16") (pintype "input"))
    )
    (net (code "68") (name "SPI-MOSI") (class "Default")
      (node (ref "CN2") (pin "8") (pinfunction "8_8") (pintype "unspecified"))
      (node (ref "U2") (pin "17") (pinfunction "PA7_17") (pintype "input"))
    )
    (net (code "69") (name "SPI-NSS") (class "Default")
      (node (ref "CN2") (pin "11") (pinfunction "11_11") (pintype "unspecified"))
      (node (ref "U2") (pin "14") (pinfunction "PA4_14") (pintype "input"))
    )
    (net (code "70") (name "UART-RTS") (class "Default")
      (node (ref "R31") (pin "2") (pinfunction "2_2") (pintype "input"))
      (node (ref "U2") (pin "11") (pinfunction "PA1_11") (pintype "input"))
    )
    (net (code "71") (name "UART-RX") (class "Default")
      (node (ref "R24") (pin "2") (pinfunction "2_2") (pintype "input"))
      (node (ref "U2") (pin "13") (pinfunction "PA3_13") (pintype "input"))
      (node (ref "U8") (pin "4") (pinfunction "VO_4") (pintype "unspecified"))
    )
    (net (code "72") (name "UART-TX") (class "Default")
      (node (ref "R28") (pin "2") (pinfunction "2_2") (pintype "input"))
      (node (ref "U2") (pin "12") (pinfunction "PA2_12") (pintype "input"))
    )
    (net (code "73") (name "USB-VBUS") (class "Default")
      (node (ref "C15") (pin "2") (pinfunction "2_2") (pintype "input"))
      (node (ref "C22") (pin "1") (pinfunction "1_1") (pintype "input"))
      (node (ref "C23") (pin "1") (pinfunction "1_1") (pintype "input"))
      (node (ref "C5") (pin "2") (pinfunction "2_2") (pintype "input"))
      (node (ref "C6") (pin "2") (pinfunction "2_2") (pintype "unspecified"))
      (node (ref "H2") (pin "5") (pinfunction "5_5") (pintype "unspecified"))
      (node (ref "R11") (pin "2") (pinfunction "2_2") (pintype "input"))
      (node (ref "U1") (pin "12") (pinfunction "V5_12") (pintype "unspecified"))
      (node (ref "U3") (pin "4") (pinfunction "IN_4") (pintype "input"))
      (node (ref "USB1") (pin "11") (pinfunction "VBUS_11") (pintype "unspecified"))
      (node (ref "USB1") (pin "2") (pinfunction "VBUS_2") (pintype "unspecified"))
      (node (ref "USB2") (pin "1") (pinfunction "VCC_1") (pintype "unspecified"))
      (node (ref "USB3") (pin "1") (pinfunction "VCC_1") (pintype "unspecified"))
    )
    (net (code "74") (name "unconnected-(H2-Pad3)") (class "Default")
      (node (ref "H2") (pin "3") (pinfunction "3_3") (pintype "unspecified+no_connect"))
    )
    (net (code "75") (name "unconnected-(U1-RESET#{slash}CDP-Pad9)") (class "Default")
      (node (ref "U1") (pin "9") (pinfunction "RESET#/CDP_9") (pintype "unspecified+no_connect"))
    )
    (net (code "76") (name "unconnected-(U2-PA8-Pad29)") (class "Default")
      (node (ref "U2") (pin "29") (pinfunction "PA8_29") (pintype "input"))
    )
    (net (code "77") (name "unconnected-(U2-PA15-Pad38)") (class "Default")
      (node (ref "U2") (pin "38") (pinfunction "PA15_38") (pintype "input"))
    )
    (net (code "78") (name "unconnected-(U2-PB1-Pad19)") (class "Default")
      (node (ref "U2") (pin "19") (pinfunction "PB1_19") (pintype "input"))
    )
    (net (code "79") (name "unconnected-(U2-PB2-Pad20)") (class "Default")
      (node (ref "U2") (pin "20") (pinfunction "PB2_20") (pintype "input"))
    )
    (net (code "80") (name "unconnected-(U2-PB3-Pad39)") (class "Default")
      (node (ref "U2") (pin "39") (pinfunction "PB3_39") (pintype "input"))
    )
    (net (code "81") (name "unconnected-(U2-PB4-Pad40)") (class "Default")
      (node (ref "U2") (pin "40") (pinfunction "PB4_40") (pintype "input"))
    )
    (net (code "82") (name "unconnected-(U2-PB5-Pad41)") (class "Default")
      (node (ref "U2") (pin "41") (pinfunction "PB5_41") (pintype "input"))
    )
    (net (code "83") (name "unconnected-(U2-PB6-Pad42)") (class "Default")
      (node (ref "U2") (pin "42") (pinfunction "PB6_42") (pintype "input"))
    )
    (net (code "84") (name "unconnected-(U2-PB7-Pad43)") (class "Default")
      (node (ref "U2") (pin "43") (pinfunction "PB7_43") (pintype "input"))
    )
    (net (code "85") (name "unconnected-(U2-PB12-Pad25)") (class "Default")
      (node (ref "U2") (pin "25") (pinfunction "PB12_25") (pintype "input"))
    )
    (net (code "86") (name "unconnected-(U2-PB13-Pad26)") (class "Default")
      (node (ref "U2") (pin "26") (pinfunction "PB13_26") (pintype "input"))
    )
    (net (code "87") (name "unconnected-(U2-PB14-Pad27)") (class "Default")
      (node (ref "U2") (pin "27") (pinfunction "PB14_27") (pintype "input"))
    )
    (net (code "88") (name "unconnected-(U2-PB15-Pad28)") (class "Default")
      (node (ref "U2") (pin "28") (pinfunction "PB15_28") (pintype "input"))
    )
    (net (code "89") (name "unconnected-(U2-PC13-TAMPERRTC-Pad2)") (class "Default")
      (node (ref "U2") (pin "2") (pinfunction "PC13-TAMPERRTC_2") (pintype "input"))
    )
    (net (code "90") (name "unconnected-(U2-PC14-OSC32_IN-Pad3)") (class "Default")
      (node (ref "U2") (pin "3") (pinfunction "PC14-OSC32_IN_3") (pintype "input"))
    )
    (net (code "91") (name "unconnected-(U2-PC15-OSC32_OUT-Pad4)") (class "Default")
      (node (ref "U2") (pin "4") (pinfunction "PC15-OSC32_OUT_4") (pintype "input"))
    )
    (net (code "92") (name "unconnected-(U4-PA1-Pad11)") (class "Default")
      (node (ref "U4") (pin "11") (pinfunction "PA1_11") (pintype "input"))
    )
    (net (code "93") (name "unconnected-(U4-PA4-Pad14)") (class "Default")
      (node (ref "U4") (pin "14") (pinfunction "PA4_14") (pintype "input"))
    )
    (net (code "94") (name "unconnected-(U4-PA5-Pad15)") (class "Default")
      (node (ref "U4") (pin "15") (pinfunction "PA5_15") (pintype "input"))
    )
    (net (code "95") (name "unconnected-(U4-PA6-Pad16)") (class "Default")
      (node (ref "U4") (pin "16") (pinfunction "PA6_16") (pintype "input"))
    )
    (net (code "96") (name "unconnected-(U4-PA7-Pad17)") (class "Default")
      (node (ref "U4") (pin "17") (pinfunction "PA7_17") (pintype "input"))
    )
    (net (code "97") (name "unconnected-(U4-PA8-Pad29)") (class "Default")
      (node (ref "U4") (pin "29") (pinfunction "PA8_29") (pintype "input"))
    )
    (net (code "98") (name "unconnected-(U4-PA15-Pad38)") (class "Default")
      (node (ref "U4") (pin "38") (pinfunction "PA15_38") (pintype "input"))
    )
    (net (code "99") (name "unconnected-(U4-PB1-Pad19)") (class "Default")
      (node (ref "U4") (pin "19") (pinfunction "PB1_19") (pintype "input"))
    )
    (net (code "100") (name "unconnected-(U4-PB3-Pad39)") (class "Default")
      (node (ref "U4") (pin "39") (pinfunction "PB3_39") (pintype "input"))
    )
    (net (code "101") (name "unconnected-(U4-PB4-Pad40)") (class "Default")
      (node (ref "U4") (pin "40") (pinfunction "PB4_40") (pintype "input"))
    )
    (net (code "102") (name "unconnected-(U4-PB5-Pad41)") (class "Default")
      (node (ref "U4") (pin "41") (pinfunction "PB5_41") (pintype "input"))
    )
    (net (code "103") (name "unconnected-(U4-PB6-Pad42)") (class "Default")
      (node (ref "U4") (pin "42") (pinfunction "PB6_42") (pintype "input"))
    )
    (net (code "104") (name "unconnected-(U4-PB7-Pad43)") (class "Default")
      (node (ref "U4") (pin "43") (pinfunction "PB7_43") (pintype "input"))
    )
    (net (code "105") (name "unconnected-(U4-PB8-Pad45)") (class "Default")
      (node (ref "U4") (pin "45") (pinfunction "PB8_45") (pintype "input"))
    )
    (net (code "106") (name "unconnected-(U4-PB9-Pad46)") (class "Default")
      (node (ref "U4") (pin "46") (pinfunction "PB9_46") (pintype "input"))
    )
    (net (code "107") (name "unconnected-(U4-PB15-Pad28)") (class "Default")
      (node (ref "U4") (pin "28") (pinfunction "PB15_28") (pintype "input"))
    )
    (net (code "108") (name "unconnected-(U4-PC13-TAMPERRTC-Pad2)") (class "Default")
      (node (ref "U4") (pin "2") (pinfunction "PC13-TAMPERRTC_2") (pintype "input"))
    )
    (net (code "109") (name "unconnected-(U4-PC14-OSC32_IN-Pad3)") (class "Default")
      (node (ref "U4") (pin "3") (pinfunction "PC14-OSC32_IN_3") (pintype "input"))
    )
    (net (code "110") (name "unconnected-(U4-PC15-OSC32_OUT-Pad4)") (class "Default")
      (node (ref "U4") (pin "4") (pinfunction "PC15-OSC32_OUT_4") (pintype "input"))
    )
    (net (code "111") (name "unconnected-(U9-NC-Pad1)") (class "Default")
      (node (ref "U9") (pin "1") (pinfunction "NC_1") (pintype "unspecified+no_connect"))
    )
    (net (code "112") (name "unconnected-(U9-NC-Pad6)") (class "Default")
      (node (ref "U9") (pin "6") (pinfunction "NC_6") (pintype "unspecified+no_connect"))
    )
    (net (code "113") (name "unconnected-(USB1-SBU1-Pad9)") (class "Default")
      (node (ref "USB1") (pin "9") (pinfunction "SBU1_9") (pintype "unspecified+no_connect"))
    )
    (net (code "114") (name "unconnected-(USB1-SBU2-Pad3)") (class "Default")
      (node (ref "USB1") (pin "3") (pinfunction "SBU2_3") (pintype "unspecified+no_connect"))
    )
  )
)
